# Frequenzweiche.net
KiCad netlist of a schematic drawn in Altium Designer
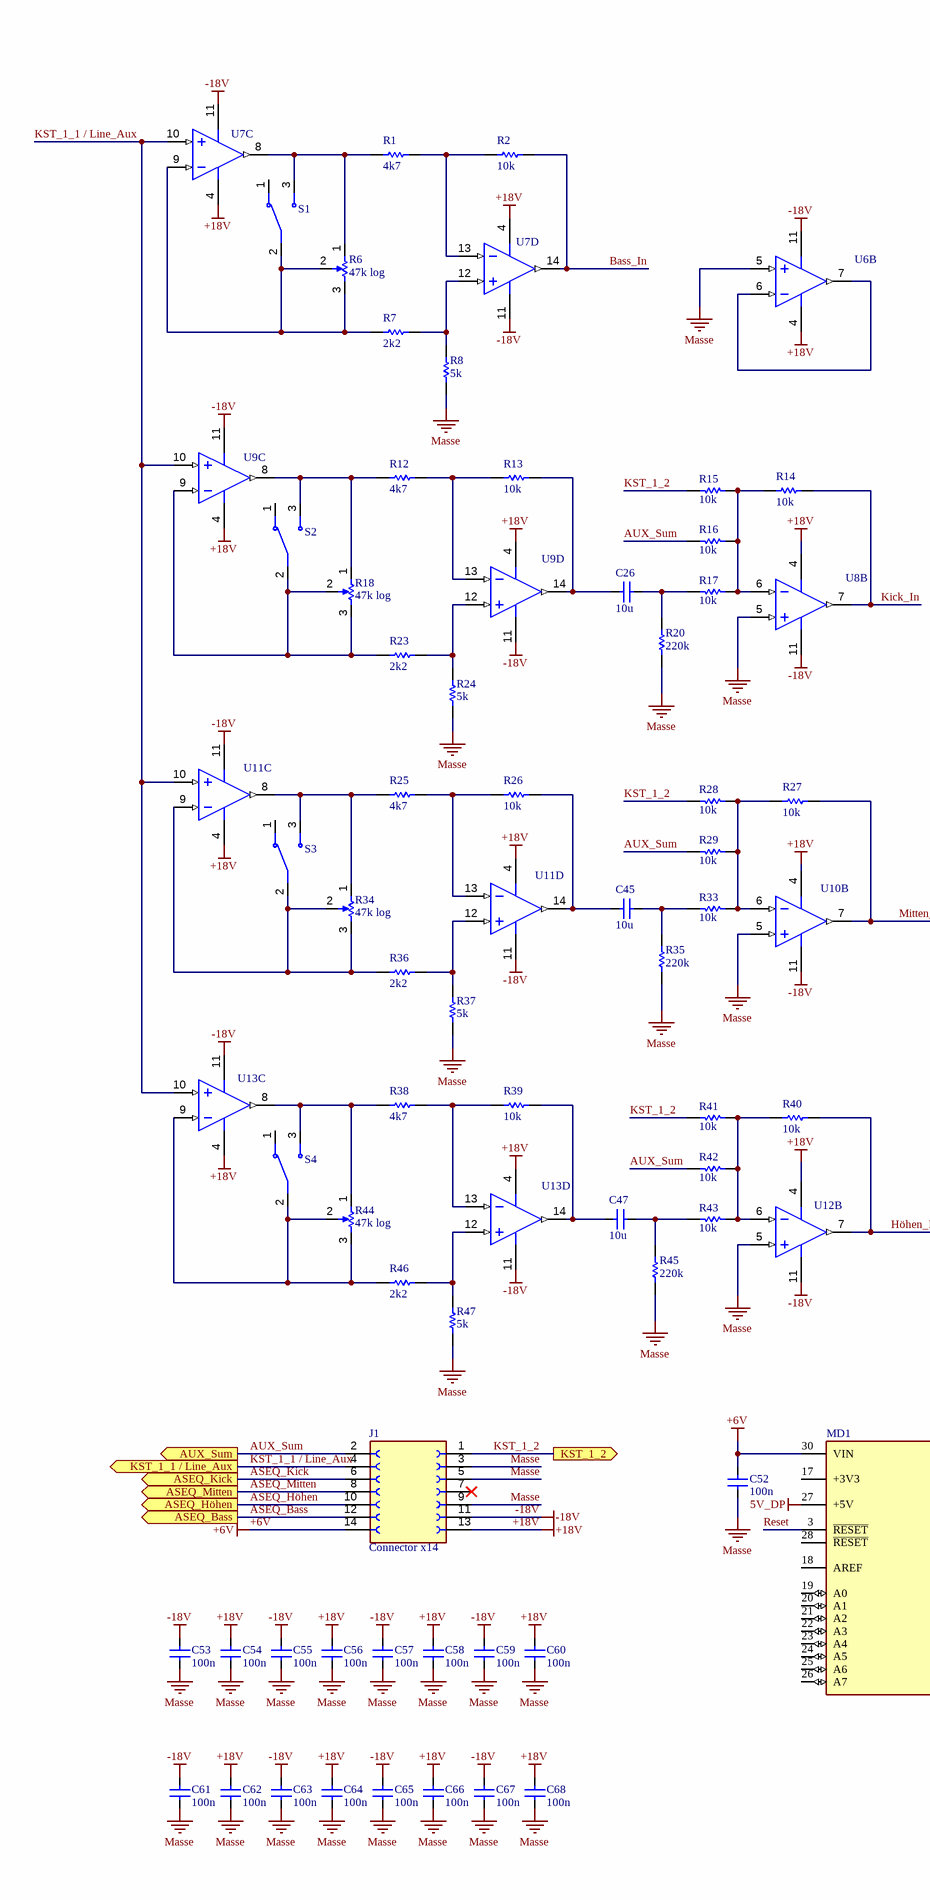
[diagram p0: Frequenzweiche.SchDoc, left]
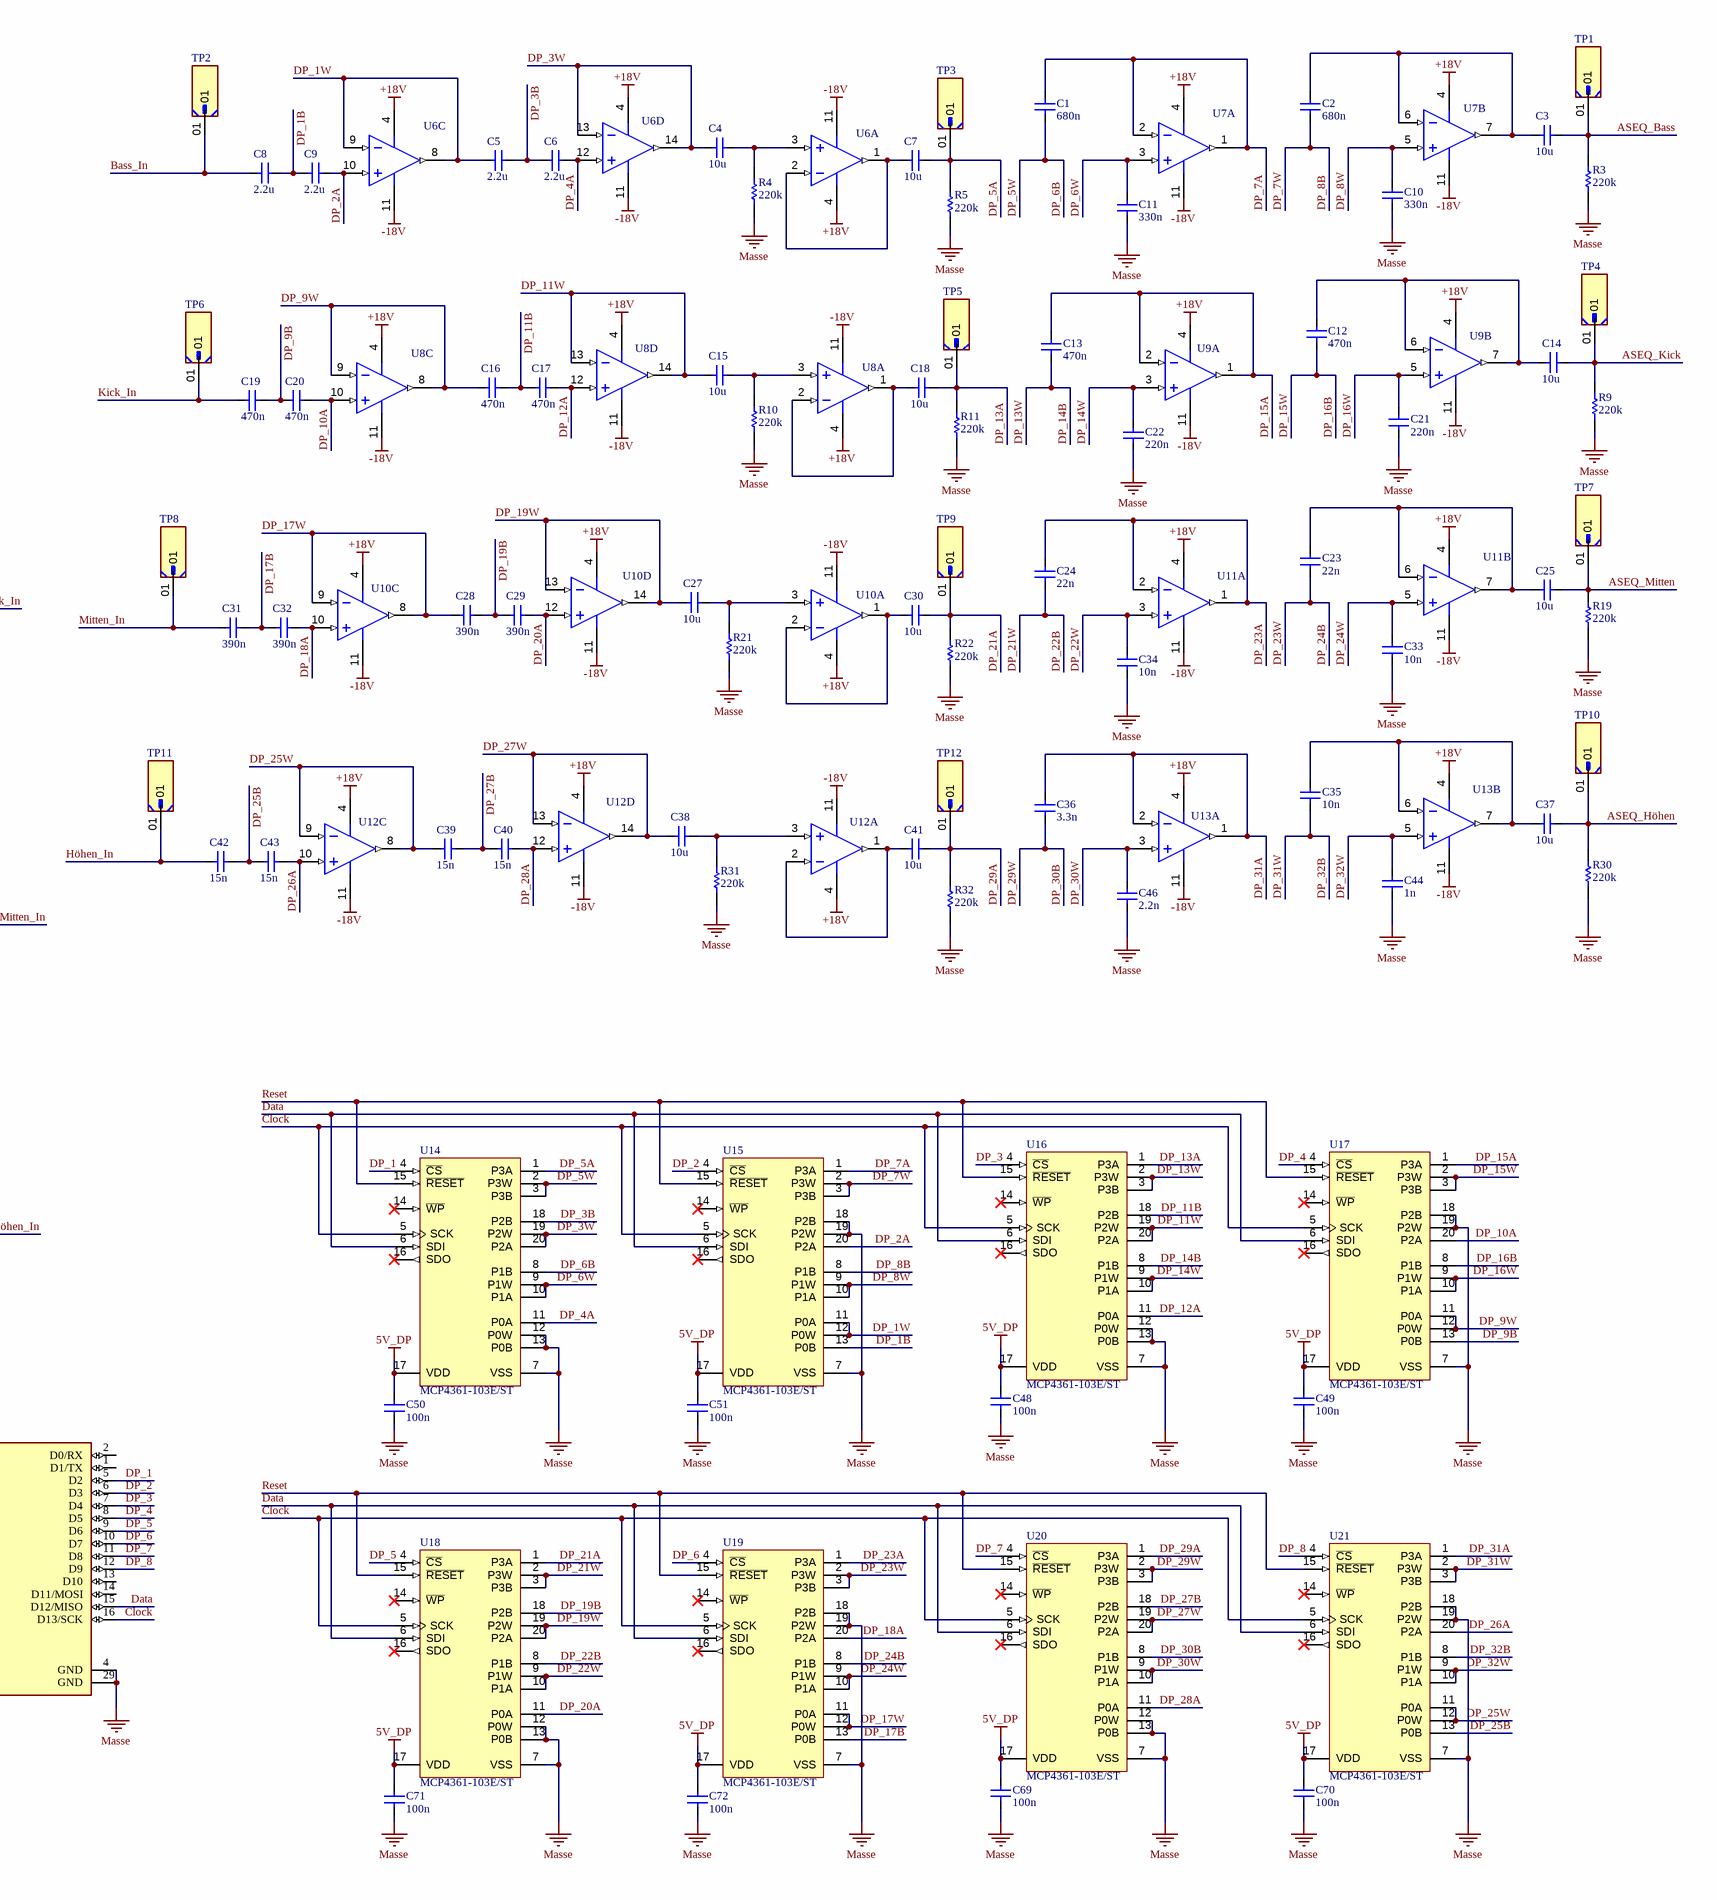
[diagram p1: Frequenzweiche.SchDoc, right]

(export (version "E")
  (design (tool "Eeschema 10.0.6"))
  (components
    (comp (ref "C1")
      (value "680n")
      (footprint "0805")
      (description "0805 Kondensator")
      (libsource (lib "Bauteile") (part "0805 Kondensator"))
    )
    (comp (ref "C2")
      (value "680n")
      (footprint "0805")
      (description "0805 Kondensator")
      (libsource (lib "Bauteile") (part "0805 Kondensator"))
    )
    (comp (ref "C3")
      (value "10u")
      (footprint "0805")
      (description "0805 Kondensator")
      (libsource (lib "Bauteile") (part "0805 Kondensator"))
    )
    (comp (ref "C4")
      (value "10u")
      (footprint "0805")
      (description "0805 Kondensator")
      (libsource (lib "Bauteile") (part "0805 Kondensator"))
    )
    (comp (ref "C5")
      (value "2.2u")
      (footprint "0805")
      (description "0805 Kondensator")
      (libsource (lib "Bauteile") (part "0805 Kondensator"))
    )
    (comp (ref "C6")
      (value "2.2u")
      (footprint "0805")
      (description "0805 Kondensator")
      (libsource (lib "Bauteile") (part "0805 Kondensator"))
    )
    (comp (ref "C7")
      (value "10u")
      (footprint "0805")
      (description "0805 Kondensator")
      (libsource (lib "Bauteile") (part "0805 Kondensator"))
    )
    (comp (ref "C8")
      (value "2.2u")
      (footprint "0805")
      (description "0805 Kondensator")
      (libsource (lib "Bauteile") (part "0805 Kondensator"))
    )
    (comp (ref "C9")
      (value "2.2u")
      (footprint "0805")
      (description "0805 Kondensator")
      (libsource (lib "Bauteile") (part "0805 Kondensator"))
    )
    (comp (ref "C10")
      (value "330n")
      (footprint "0805")
      (description "0805 Kondensator")
      (libsource (lib "Bauteile") (part "0805 Kondensator"))
    )
    (comp (ref "C11")
      (value "330n")
      (footprint "0805")
      (description "0805 Kondensator")
      (libsource (lib "Bauteile") (part "0805 Kondensator"))
    )
    (comp (ref "C12")
      (value "470n")
      (footprint "0805")
      (description "0805 Kondensator")
      (libsource (lib "Bauteile") (part "0805 Kondensator"))
    )
    (comp (ref "C13")
      (value "470n")
      (footprint "0805")
      (description "0805 Kondensator")
      (libsource (lib "Bauteile") (part "0805 Kondensator"))
    )
    (comp (ref "C14")
      (value "10u")
      (footprint "0805")
      (description "0805 Kondensator")
      (libsource (lib "Bauteile") (part "0805 Kondensator"))
    )
    (comp (ref "C15")
      (value "10u")
      (footprint "0805")
      (description "0805 Kondensator")
      (libsource (lib "Bauteile") (part "0805 Kondensator"))
    )
    (comp (ref "C16")
      (value "470n")
      (footprint "0805")
      (description "0805 Kondensator")
      (libsource (lib "Bauteile") (part "0805 Kondensator"))
    )
    (comp (ref "C17")
      (value "470n")
      (footprint "0805")
      (description "0805 Kondensator")
      (libsource (lib "Bauteile") (part "0805 Kondensator"))
    )
    (comp (ref "C18")
      (value "10u")
      (footprint "0805")
      (description "0805 Kondensator")
      (libsource (lib "Bauteile") (part "0805 Kondensator"))
    )
    (comp (ref "C19")
      (value "470n")
      (footprint "0805")
      (description "0805 Kondensator")
      (libsource (lib "Bauteile") (part "0805 Kondensator"))
    )
    (comp (ref "C20")
      (value "470n")
      (footprint "0805")
      (description "0805 Kondensator")
      (libsource (lib "Bauteile") (part "0805 Kondensator"))
    )
    (comp (ref "C21")
      (value "220n")
      (footprint "0805")
      (description "0805 Kondensator")
      (libsource (lib "Bauteile") (part "0805 Kondensator"))
    )
    (comp (ref "C22")
      (value "220n")
      (footprint "0805")
      (description "0805 Kondensator")
      (libsource (lib "Bauteile") (part "0805 Kondensator"))
    )
    (comp (ref "C23")
      (value "22n")
      (footprint "0805")
      (description "0805 Kondensator")
      (libsource (lib "Bauteile") (part "0805 Kondensator"))
    )
    (comp (ref "C24")
      (value "22n")
      (footprint "0805")
      (description "0805 Kondensator")
      (libsource (lib "Bauteile") (part "0805 Kondensator"))
    )
    (comp (ref "C25")
      (value "10u")
      (footprint "0805")
      (description "0805 Kondensator")
      (libsource (lib "Bauteile") (part "0805 Kondensator"))
    )
    (comp (ref "C26")
      (value "10u")
      (footprint "0805")
      (description "0805 Kondensator")
      (libsource (lib "Bauteile") (part "0805 Kondensator"))
    )
    (comp (ref "C27")
      (value "10u")
      (footprint "0805")
      (description "0805 Kondensator")
      (libsource (lib "Bauteile") (part "0805 Kondensator"))
    )
    (comp (ref "C28")
      (value "390n")
      (footprint "0805")
      (description "0805 Kondensator")
      (libsource (lib "Bauteile") (part "0805 Kondensator"))
    )
    (comp (ref "C29")
      (value "390n")
      (footprint "0805")
      (description "0805 Kondensator")
      (libsource (lib "Bauteile") (part "0805 Kondensator"))
    )
    (comp (ref "C30")
      (value "10u")
      (footprint "0805")
      (description "0805 Kondensator")
      (libsource (lib "Bauteile") (part "0805 Kondensator"))
    )
    (comp (ref "C31")
      (value "390n")
      (footprint "0805")
      (description "0805 Kondensator")
      (libsource (lib "Bauteile") (part "0805 Kondensator"))
    )
    (comp (ref "C32")
      (value "390n")
      (footprint "0805")
      (description "0805 Kondensator")
      (libsource (lib "Bauteile") (part "0805 Kondensator"))
    )
    (comp (ref "C33")
      (value "10n")
      (footprint "0805")
      (description "0805 Kondensator")
      (libsource (lib "Bauteile") (part "0805 Kondensator"))
    )
    (comp (ref "C34")
      (value "10n")
      (footprint "0805")
      (description "0805 Kondensator")
      (libsource (lib "Bauteile") (part "0805 Kondensator"))
    )
    (comp (ref "C35")
      (value "10n")
      (footprint "0805")
      (description "0805 Kondensator")
      (libsource (lib "Bauteile") (part "0805 Kondensator"))
    )
    (comp (ref "C36")
      (value "3.3n")
      (footprint "0805")
      (description "0805 Kondensator")
      (libsource (lib "Bauteile") (part "0805 Kondensator"))
    )
    (comp (ref "C37")
      (value "10u")
      (footprint "0805")
      (description "0805 Kondensator")
      (libsource (lib "Bauteile") (part "0805 Kondensator"))
    )
    (comp (ref "C38")
      (value "10u")
      (footprint "0805")
      (description "0805 Kondensator")
      (libsource (lib "Bauteile") (part "0805 Kondensator"))
    )
    (comp (ref "C39")
      (value "15n")
      (footprint "0805")
      (description "0805 Kondensator")
      (libsource (lib "Bauteile") (part "0805 Kondensator"))
    )
    (comp (ref "C40")
      (value "15n")
      (footprint "0805")
      (description "0805 Kondensator")
      (libsource (lib "Bauteile") (part "0805 Kondensator"))
    )
    (comp (ref "C41")
      (value "10u")
      (footprint "0805")
      (description "0805 Kondensator")
      (libsource (lib "Bauteile") (part "0805 Kondensator"))
    )
    (comp (ref "C42")
      (value "15n")
      (footprint "0805")
      (description "0805 Kondensator")
      (libsource (lib "Bauteile") (part "0805 Kondensator"))
    )
    (comp (ref "C43")
      (value "15n")
      (footprint "0805")
      (description "0805 Kondensator")
      (libsource (lib "Bauteile") (part "0805 Kondensator"))
    )
    (comp (ref "C44")
      (value "1n")
      (footprint "0805")
      (description "0805 Kondensator")
      (libsource (lib "Bauteile") (part "0805 Kondensator"))
    )
    (comp (ref "C45")
      (value "10u")
      (footprint "0805")
      (description "0805 Kondensator")
      (libsource (lib "Bauteile") (part "0805 Kondensator"))
    )
    (comp (ref "C46")
      (value "2.2n")
      (footprint "0805")
      (description "0805 Kondensator")
      (libsource (lib "Bauteile") (part "0805 Kondensator"))
    )
    (comp (ref "C47")
      (value "10u")
      (footprint "0805")
      (description "0805 Kondensator")
      (libsource (lib "Bauteile") (part "0805 Kondensator"))
    )
    (comp (ref "C48")
      (value "100n")
      (footprint "0805")
      (description "0805 Kondensator")
      (libsource (lib "Bauteile") (part "0805 Kondensator"))
    )
    (comp (ref "C49")
      (value "100n")
      (footprint "0805")
      (description "0805 Kondensator")
      (libsource (lib "Bauteile") (part "0805 Kondensator"))
    )
    (comp (ref "C50")
      (value "100n")
      (footprint "0805")
      (description "0805 Kondensator")
      (libsource (lib "Bauteile") (part "0805 Kondensator"))
    )
    (comp (ref "C51")
      (value "100n")
      (footprint "0805")
      (description "0805 Kondensator")
      (libsource (lib "Bauteile") (part "0805 Kondensator"))
    )
    (comp (ref "C52")
      (value "100n")
      (footprint "0805")
      (description "0805 Kondensator")
      (libsource (lib "Bauteile") (part "0805 Kondensator"))
    )
    (comp (ref "C53")
      (value "100n")
      (footprint "0805")
      (description "0805 Kondensator")
      (libsource (lib "Bauteile") (part "0805 Kondensator"))
    )
    (comp (ref "C54")
      (value "100n")
      (footprint "0805")
      (description "0805 Kondensator")
      (libsource (lib "Bauteile") (part "0805 Kondensator"))
    )
    (comp (ref "C55")
      (value "100n")
      (footprint "0805")
      (description "0805 Kondensator")
      (libsource (lib "Bauteile") (part "0805 Kondensator"))
    )
    (comp (ref "C56")
      (value "100n")
      (footprint "0805")
      (description "0805 Kondensator")
      (libsource (lib "Bauteile") (part "0805 Kondensator"))
    )
    (comp (ref "C57")
      (value "100n")
      (footprint "0805")
      (description "0805 Kondensator")
      (libsource (lib "Bauteile") (part "0805 Kondensator"))
    )
    (comp (ref "C58")
      (value "100n")
      (footprint "0805")
      (description "0805 Kondensator")
      (libsource (lib "Bauteile") (part "0805 Kondensator"))
    )
    (comp (ref "C59")
      (value "100n")
      (footprint "0805")
      (description "0805 Kondensator")
      (libsource (lib "Bauteile") (part "0805 Kondensator"))
    )
    (comp (ref "C60")
      (value "100n")
      (footprint "0805")
      (description "0805 Kondensator")
      (libsource (lib "Bauteile") (part "0805 Kondensator"))
    )
    (comp (ref "C61")
      (value "100n")
      (footprint "0805")
      (description "0805 Kondensator")
      (libsource (lib "Bauteile") (part "0805 Kondensator"))
    )
    (comp (ref "C62")
      (value "100n")
      (footprint "0805")
      (description "0805 Kondensator")
      (libsource (lib "Bauteile") (part "0805 Kondensator"))
    )
    (comp (ref "C63")
      (value "100n")
      (footprint "0805")
      (description "0805 Kondensator")
      (libsource (lib "Bauteile") (part "0805 Kondensator"))
    )
    (comp (ref "C64")
      (value "100n")
      (footprint "0805")
      (description "0805 Kondensator")
      (libsource (lib "Bauteile") (part "0805 Kondensator"))
    )
    (comp (ref "C65")
      (value "100n")
      (footprint "0805")
      (description "0805 Kondensator")
      (libsource (lib "Bauteile") (part "0805 Kondensator"))
    )
    (comp (ref "C66")
      (value "100n")
      (footprint "0805")
      (description "0805 Kondensator")
      (libsource (lib "Bauteile") (part "0805 Kondensator"))
    )
    (comp (ref "C67")
      (value "100n")
      (footprint "0805")
      (description "0805 Kondensator")
      (libsource (lib "Bauteile") (part "0805 Kondensator"))
    )
    (comp (ref "C68")
      (value "100n")
      (footprint "0805")
      (description "0805 Kondensator")
      (libsource (lib "Bauteile") (part "0805 Kondensator"))
    )
    (comp (ref "C69")
      (value "100n")
      (footprint "0805")
      (description "0805 Kondensator")
      (libsource (lib "Bauteile") (part "0805 Kondensator"))
    )
    (comp (ref "C70")
      (value "100n")
      (footprint "0805")
      (description "0805 Kondensator")
      (libsource (lib "Bauteile") (part "0805 Kondensator"))
    )
    (comp (ref "C71")
      (value "100n")
      (footprint "0805")
      (description "0805 Kondensator")
      (libsource (lib "Bauteile") (part "0805 Kondensator"))
    )
    (comp (ref "C72")
      (value "100n")
      (footprint "0805")
      (description "0805 Kondensator")
      (libsource (lib "Bauteile") (part "0805 Kondensator"))
    )
    (comp (ref "J1")
      (value "Connector x14")
      (footprint "Connector x14")
      (description "14 Position Header Connector Through Hole")
      (fields (field (name "MF") "Sullins Connector") (field (name "MP") "SFH11-PBPC-D07-ST-BK"))
      (libsource (lib "Bauteile") (part "Connector x14"))
    )
    (comp (ref "MD1")
      (value "A000005")
      (footprint "Arduino Nano")
      (description "ARDUINO NANO ATMEGA328 EVAL BRD")
      (libsource (lib "Bauteile") (part "Arduino Nano"))
    )
    (comp (ref "R1")
      (value "4k7")
      (footprint "0805")
      (description "0805 Widerstand")
      (libsource (lib "Bauteile") (part "0805 Widerstand"))
    )
    (comp (ref "R2")
      (value "10k")
      (footprint "0805")
      (description "0805 Widerstand")
      (libsource (lib "Bauteile") (part "0805 Widerstand"))
    )
    (comp (ref "R3")
      (value "220k")
      (footprint "0805")
      (description "0805 Widerstand")
      (libsource (lib "Bauteile") (part "0805 Widerstand"))
    )
    (comp (ref "R4")
      (value "220k")
      (footprint "0805")
      (description "0805 Widerstand")
      (libsource (lib "Bauteile") (part "0805 Widerstand"))
    )
    (comp (ref "R5")
      (value "220k")
      (footprint "0805")
      (description "0805 Widerstand")
      (libsource (lib "Bauteile") (part "0805 Widerstand"))
    )
    (comp (ref "R6")
      (value "47k log")
      (footprint "Connector x3")
      (description "Potentiometer")
      (libsource (lib "Bauteile") (part "Potentiometer Buchsenleiste"))
    )
    (comp (ref "R7")
      (value "2k2")
      (footprint "0805")
      (description "0805 Widerstand")
      (libsource (lib "Bauteile") (part "0805 Widerstand"))
    )
    (comp (ref "R8")
      (value "5k")
      (footprint "0805")
      (description "0805 Widerstand")
      (libsource (lib "Bauteile") (part "0805 Widerstand"))
    )
    (comp (ref "R9")
      (value "220k")
      (footprint "0805")
      (description "0805 Widerstand")
      (libsource (lib "Bauteile") (part "0805 Widerstand"))
    )
    (comp (ref "R10")
      (value "220k")
      (footprint "0805")
      (description "0805 Widerstand")
      (libsource (lib "Bauteile") (part "0805 Widerstand"))
    )
    (comp (ref "R11")
      (value "220k")
      (footprint "0805")
      (description "0805 Widerstand")
      (libsource (lib "Bauteile") (part "0805 Widerstand"))
    )
    (comp (ref "R12")
      (value "4k7")
      (footprint "0805")
      (description "0805 Widerstand")
      (libsource (lib "Bauteile") (part "0805 Widerstand"))
    )
    (comp (ref "R13")
      (value "10k")
      (footprint "0805")
      (description "0805 Widerstand")
      (libsource (lib "Bauteile") (part "0805 Widerstand"))
    )
    (comp (ref "R14")
      (value "10k")
      (footprint "0805")
      (description "0805 Widerstand")
      (libsource (lib "Bauteile") (part "0805 Widerstand"))
    )
    (comp (ref "R15")
      (value "10k")
      (footprint "0805")
      (description "0805 Widerstand")
      (libsource (lib "Bauteile") (part "0805 Widerstand"))
    )
    (comp (ref "R16")
      (value "10k")
      (footprint "0805")
      (description "0805 Widerstand")
      (libsource (lib "Bauteile") (part "0805 Widerstand"))
    )
    (comp (ref "R17")
      (value "10k")
      (footprint "0805")
      (description "0805 Widerstand")
      (libsource (lib "Bauteile") (part "0805 Widerstand"))
    )
    (comp (ref "R18")
      (value "47k log")
      (footprint "Connector x3")
      (description "Potentiometer")
      (libsource (lib "Bauteile") (part "Potentiometer Buchsenleiste"))
    )
    (comp (ref "R19")
      (value "220k")
      (footprint "0805")
      (description "0805 Widerstand")
      (libsource (lib "Bauteile") (part "0805 Widerstand"))
    )
    (comp (ref "R20")
      (value "220k")
      (footprint "0805")
      (description "0805 Widerstand")
      (libsource (lib "Bauteile") (part "0805 Widerstand"))
    )
    (comp (ref "R21")
      (value "220k")
      (footprint "0805")
      (description "0805 Widerstand")
      (libsource (lib "Bauteile") (part "0805 Widerstand"))
    )
    (comp (ref "R22")
      (value "220k")
      (footprint "0805")
      (description "0805 Widerstand")
      (libsource (lib "Bauteile") (part "0805 Widerstand"))
    )
    (comp (ref "R23")
      (value "2k2")
      (footprint "0805")
      (description "0805 Widerstand")
      (libsource (lib "Bauteile") (part "0805 Widerstand"))
    )
    (comp (ref "R24")
      (value "5k")
      (footprint "0805")
      (description "0805 Widerstand")
      (libsource (lib "Bauteile") (part "0805 Widerstand"))
    )
    (comp (ref "R25")
      (value "4k7")
      (footprint "0805")
      (description "0805 Widerstand")
      (libsource (lib "Bauteile") (part "0805 Widerstand"))
    )
    (comp (ref "R26")
      (value "10k")
      (footprint "0805")
      (description "0805 Widerstand")
      (libsource (lib "Bauteile") (part "0805 Widerstand"))
    )
    (comp (ref "R27")
      (value "10k")
      (footprint "0805")
      (description "0805 Widerstand")
      (libsource (lib "Bauteile") (part "0805 Widerstand"))
    )
    (comp (ref "R28")
      (value "10k")
      (footprint "0805")
      (description "0805 Widerstand")
      (libsource (lib "Bauteile") (part "0805 Widerstand"))
    )
    (comp (ref "R29")
      (value "10k")
      (footprint "0805")
      (description "0805 Widerstand")
      (libsource (lib "Bauteile") (part "0805 Widerstand"))
    )
    (comp (ref "R30")
      (value "220k")
      (footprint "0805")
      (description "0805 Widerstand")
      (libsource (lib "Bauteile") (part "0805 Widerstand"))
    )
    (comp (ref "R31")
      (value "220k")
      (footprint "0805")
      (description "0805 Widerstand")
      (libsource (lib "Bauteile") (part "0805 Widerstand"))
    )
    (comp (ref "R32")
      (value "220k")
      (footprint "0805")
      (description "0805 Widerstand")
      (libsource (lib "Bauteile") (part "0805 Widerstand"))
    )
    (comp (ref "R33")
      (value "10k")
      (footprint "0805")
      (description "0805 Widerstand")
      (libsource (lib "Bauteile") (part "0805 Widerstand"))
    )
    (comp (ref "R34")
      (value "47k log")
      (footprint "Connector x3")
      (description "Potentiometer")
      (libsource (lib "Bauteile") (part "Potentiometer Buchsenleiste"))
    )
    (comp (ref "R35")
      (value "220k")
      (footprint "0805")
      (description "0805 Widerstand")
      (libsource (lib "Bauteile") (part "0805 Widerstand"))
    )
    (comp (ref "R36")
      (value "2k2")
      (footprint "0805")
      (description "0805 Widerstand")
      (libsource (lib "Bauteile") (part "0805 Widerstand"))
    )
    (comp (ref "R37")
      (value "5k")
      (footprint "0805")
      (description "0805 Widerstand")
      (libsource (lib "Bauteile") (part "0805 Widerstand"))
    )
    (comp (ref "R38")
      (value "4k7")
      (footprint "0805")
      (description "0805 Widerstand")
      (libsource (lib "Bauteile") (part "0805 Widerstand"))
    )
    (comp (ref "R39")
      (value "10k")
      (footprint "0805")
      (description "0805 Widerstand")
      (libsource (lib "Bauteile") (part "0805 Widerstand"))
    )
    (comp (ref "R40")
      (value "10k")
      (footprint "0805")
      (description "0805 Widerstand")
      (libsource (lib "Bauteile") (part "0805 Widerstand"))
    )
    (comp (ref "R41")
      (value "10k")
      (footprint "0805")
      (description "0805 Widerstand")
      (libsource (lib "Bauteile") (part "0805 Widerstand"))
    )
    (comp (ref "R42")
      (value "10k")
      (footprint "0805")
      (description "0805 Widerstand")
      (libsource (lib "Bauteile") (part "0805 Widerstand"))
    )
    (comp (ref "R43")
      (value "10k")
      (footprint "0805")
      (description "0805 Widerstand")
      (libsource (lib "Bauteile") (part "0805 Widerstand"))
    )
    (comp (ref "R44")
      (value "47k log")
      (footprint "Connector x3")
      (description "Potentiometer")
      (libsource (lib "Bauteile") (part "Potentiometer Buchsenleiste"))
    )
    (comp (ref "R45")
      (value "220k")
      (footprint "0805")
      (description "0805 Widerstand")
      (libsource (lib "Bauteile") (part "0805 Widerstand"))
    )
    (comp (ref "R46")
      (value "2k2")
      (footprint "0805")
      (description "0805 Widerstand")
      (libsource (lib "Bauteile") (part "0805 Widerstand"))
    )
    (comp (ref "R47")
      (value "5k")
      (footprint "0805")
      (description "0805 Widerstand")
      (libsource (lib "Bauteile") (part "0805 Widerstand"))
    )
    (comp (ref "S1")
      (value "Schalter Buchsenleiste")
      (footprint "Connector x3")
      (description "Toggle Switch SPDT Through Hole")
      (fields (field (name "MP") "100SP1T1B4M2QE"))
      (libsource (lib "Bauteile") (part "Schalter Buchsenleiste"))
    )
    (comp (ref "S2")
      (value "Schalter Buchsenleiste")
      (footprint "Connector x3")
      (description "Toggle Switch SPDT Through Hole")
      (fields (field (name "MP") "100SP1T1B4M2QE"))
      (libsource (lib "Bauteile") (part "Schalter Buchsenleiste"))
    )
    (comp (ref "S3")
      (value "Schalter Buchsenleiste")
      (footprint "Connector x3")
      (description "Toggle Switch SPDT Through Hole")
      (fields (field (name "MP") "100SP1T1B4M2QE"))
      (libsource (lib "Bauteile") (part "Schalter Buchsenleiste"))
    )
    (comp (ref "S4")
      (value "Schalter Buchsenleiste")
      (footprint "Connector x3")
      (description "Toggle Switch SPDT Through Hole")
      (fields (field (name "MP") "100SP1T1B4M2QE"))
      (libsource (lib "Bauteile") (part "Schalter Buchsenleiste"))
    )
    (comp (ref "TP1")
      (value "Test_Pin")
      (footprint "Test_Pin")
      (description "Connector Header Through Hole 2 position 0.100 (2.54mm)")
      (fields (field (name "MF") "Wurth Elektronik") (field (name "MP") "61300211121"))
      (libsource (lib "Bauteile") (part "Test_Pin"))
    )
    (comp (ref "TP2")
      (value "Test_Pin")
      (footprint "Test_Pin")
      (description "Connector Header Through Hole 2 position 0.100 (2.54mm)")
      (fields (field (name "MF") "Wurth Elektronik") (field (name "MP") "61300211121"))
      (libsource (lib "Bauteile") (part "Test_Pin"))
    )
    (comp (ref "TP3")
      (value "Test_Pin")
      (footprint "Test_Pin")
      (description "Connector Header Through Hole 2 position 0.100 (2.54mm)")
      (fields (field (name "MF") "Wurth Elektronik") (field (name "MP") "61300211121"))
      (libsource (lib "Bauteile") (part "Test_Pin"))
    )
    (comp (ref "TP4")
      (value "Test_Pin")
      (footprint "Test_Pin")
      (description "Connector Header Through Hole 2 position 0.100 (2.54mm)")
      (fields (field (name "MF") "Wurth Elektronik") (field (name "MP") "61300211121"))
      (libsource (lib "Bauteile") (part "Test_Pin"))
    )
    (comp (ref "TP5")
      (value "Test_Pin")
      (footprint "Test_Pin")
      (description "Connector Header Through Hole 2 position 0.100 (2.54mm)")
      (fields (field (name "MF") "Wurth Elektronik") (field (name "MP") "61300211121"))
      (libsource (lib "Bauteile") (part "Test_Pin"))
    )
    (comp (ref "TP6")
      (value "Test_Pin")
      (footprint "Test_Pin")
      (description "Connector Header Through Hole 2 position 0.100 (2.54mm)")
      (fields (field (name "MF") "Wurth Elektronik") (field (name "MP") "61300211121"))
      (libsource (lib "Bauteile") (part "Test_Pin"))
    )
    (comp (ref "TP7")
      (value "Test_Pin")
      (footprint "Test_Pin")
      (description "Connector Header Through Hole 2 position 0.100 (2.54mm)")
      (fields (field (name "MF") "Wurth Elektronik") (field (name "MP") "61300211121"))
      (libsource (lib "Bauteile") (part "Test_Pin"))
    )
    (comp (ref "TP8")
      (value "Test_Pin")
      (footprint "Test_Pin")
      (description "Connector Header Through Hole 2 position 0.100 (2.54mm)")
      (fields (field (name "MF") "Wurth Elektronik") (field (name "MP") "61300211121"))
      (libsource (lib "Bauteile") (part "Test_Pin"))
    )
    (comp (ref "TP9")
      (value "Test_Pin")
      (footprint "Test_Pin")
      (description "Connector Header Through Hole 2 position 0.100 (2.54mm)")
      (fields (field (name "MF") "Wurth Elektronik") (field (name "MP") "61300211121"))
      (libsource (lib "Bauteile") (part "Test_Pin"))
    )
    (comp (ref "TP10")
      (value "Test_Pin")
      (footprint "Test_Pin")
      (description "Connector Header Through Hole 2 position 0.100 (2.54mm)")
      (fields (field (name "MF") "Wurth Elektronik") (field (name "MP") "61300211121"))
      (libsource (lib "Bauteile") (part "Test_Pin"))
    )
    (comp (ref "TP11")
      (value "Test_Pin")
      (footprint "Test_Pin")
      (description "Connector Header Through Hole 2 position 0.100 (2.54mm)")
      (fields (field (name "MF") "Wurth Elektronik") (field (name "MP") "61300211121"))
      (libsource (lib "Bauteile") (part "Test_Pin"))
    )
    (comp (ref "TP12")
      (value "Test_Pin")
      (footprint "Test_Pin")
      (description "Connector Header Through Hole 2 position 0.100 (2.54mm)")
      (fields (field (name "MF") "Wurth Elektronik") (field (name "MP") "61300211121"))
      (libsource (lib "Bauteile") (part "Test_Pin"))
    )
    (comp (ref "U6")
      (value "OPA4134UA")
      (footprint "DIP14 IC Socket")
      (fields (field (name "MANUFACTURER") "Texas Instruments"))
      (libsource (lib "Bauteile") (part "SOIC OPA4134UA"))
    )
    (comp (ref "U7")
      (value "OPA4134UA")
      (footprint "DIP14 IC Socket")
      (fields (field (name "MANUFACTURER") "Texas Instruments"))
      (libsource (lib "Bauteile") (part "SOIC OPA4134UA"))
    )
    (comp (ref "U8")
      (value "OPA4134UA")
      (footprint "DIP14 IC Socket")
      (fields (field (name "MANUFACTURER") "Texas Instruments"))
      (libsource (lib "Bauteile") (part "SOIC OPA4134UA"))
    )
    (comp (ref "U9")
      (value "OPA4134UA")
      (footprint "DIP14 IC Socket")
      (fields (field (name "MANUFACTURER") "Texas Instruments"))
      (libsource (lib "Bauteile") (part "SOIC OPA4134UA"))
    )
    (comp (ref "U10")
      (value "OPA4134UA")
      (footprint "DIP14 IC Socket")
      (fields (field (name "MANUFACTURER") "Texas Instruments"))
      (libsource (lib "Bauteile") (part "SOIC OPA4134UA"))
    )
    (comp (ref "U11")
      (value "OPA4134UA")
      (footprint "DIP14 IC Socket")
      (fields (field (name "MANUFACTURER") "Texas Instruments"))
      (libsource (lib "Bauteile") (part "SOIC OPA4134UA"))
    )
    (comp (ref "U12")
      (value "OPA4134UA")
      (footprint "DIP14 IC Socket")
      (fields (field (name "MANUFACTURER") "Texas Instruments"))
      (libsource (lib "Bauteile") (part "SOIC OPA4134UA"))
    )
    (comp (ref "U13")
      (value "OPA4134UA")
      (footprint "DIP14 IC Socket")
      (fields (field (name "MANUFACTURER") "Texas Instruments"))
      (libsource (lib "Bauteile") (part "SOIC OPA4134UA"))
    )
    (comp (ref "U14")
      (value "MCP4361-103E/ST")
      (footprint "MCP 4361")
      (description "7/8-Bit Quad SPI Digital POT with Non-Volatile Memory, 20-Pin TSSOP, Extended Temperature")
      (libsource (lib "Bauteile") (part "MCP 4361"))
    )
    (comp (ref "U15")
      (value "MCP4361-103E/ST")
      (footprint "MCP 4361")
      (description "7/8-Bit Quad SPI Digital POT with Non-Volatile Memory, 20-Pin TSSOP, Extended Temperature")
      (libsource (lib "Bauteile") (part "MCP 4361"))
    )
    (comp (ref "U16")
      (value "MCP4361-103E/ST")
      (footprint "MCP 4361")
      (description "7/8-Bit Quad SPI Digital POT with Non-Volatile Memory, 20-Pin TSSOP, Extended Temperature")
      (libsource (lib "Bauteile") (part "MCP 4361"))
    )
    (comp (ref "U17")
      (value "MCP4361-103E/ST")
      (footprint "MCP 4361")
      (description "7/8-Bit Quad SPI Digital POT with Non-Volatile Memory, 20-Pin TSSOP, Extended Temperature")
      (libsource (lib "Bauteile") (part "MCP 4361"))
    )
    (comp (ref "U18")
      (value "MCP4361-103E/ST")
      (footprint "MCP 4361")
      (description "7/8-Bit Quad SPI Digital POT with Non-Volatile Memory, 20-Pin TSSOP, Extended Temperature")
      (libsource (lib "Bauteile") (part "MCP 4361"))
    )
    (comp (ref "U19")
      (value "MCP4361-103E/ST")
      (footprint "MCP 4361")
      (description "7/8-Bit Quad SPI Digital POT with Non-Volatile Memory, 20-Pin TSSOP, Extended Temperature")
      (libsource (lib "Bauteile") (part "MCP 4361"))
    )
    (comp (ref "U20")
      (value "MCP4361-103E/ST")
      (footprint "MCP 4361")
      (description "7/8-Bit Quad SPI Digital POT with Non-Volatile Memory, 20-Pin TSSOP, Extended Temperature")
      (libsource (lib "Bauteile") (part "MCP 4361"))
    )
    (comp (ref "U21")
      (value "MCP4361-103E/ST")
      (footprint "MCP 4361")
      (description "7/8-Bit Quad SPI Digital POT with Non-Volatile Memory, 20-Pin TSSOP, Extended Temperature")
      (libsource (lib "Bauteile") (part "MCP 4361"))
    )
  )
  (nets
    (net (code "1") (name "+6V") (class "Default")
      (node (ref "C52") (pin "2") (pinfunction "2_2") (pintype "passive"))
      (node (ref "J1") (pin "14") (pinfunction "14_14") (pintype "passive"))
      (node (ref "MD1") (pin "30") (pinfunction "VIN_30") (pintype "power_in"))
    )
    (net (code "2") (name "+18V") (class "Default")
      (node (ref "C54") (pin "2") (pinfunction "2_2") (pintype "passive"))
      (node (ref "C56") (pin "2") (pinfunction "2_2") (pintype "passive"))
      (node (ref "C58") (pin "2") (pinfunction "2_2") (pintype "passive"))
      (node (ref "C60") (pin "2") (pinfunction "2_2") (pintype "passive"))
      (node (ref "C62") (pin "2") (pinfunction "2_2") (pintype "passive"))
      (node (ref "C64") (pin "2") (pinfunction "2_2") (pintype "passive"))
      (node (ref "C66") (pin "2") (pinfunction "2_2") (pintype "passive"))
      (node (ref "C68") (pin "2") (pinfunction "2_2") (pintype "passive"))
      (node (ref "J1") (pin "13") (pinfunction "13_13") (pintype "passive"))
      (node (ref "U10") (pin "4") (pinfunction "V+_4") (pintype "power_in"))
      (node (ref "U11") (pin "4") (pinfunction "V+_4") (pintype "power_in"))
      (node (ref "U12") (pin "4") (pinfunction "V+_4") (pintype "power_in"))
      (node (ref "U13") (pin "4") (pinfunction "V+_4") (pintype "power_in"))
      (node (ref "U6") (pin "4") (pinfunction "V+_4") (pintype "power_in"))
      (node (ref "U7") (pin "4") (pinfunction "V+_4") (pintype "power_in"))
      (node (ref "U8") (pin "4") (pinfunction "V+_4") (pintype "power_in"))
      (node (ref "U9") (pin "4") (pinfunction "V+_4") (pintype "power_in"))
    )
    (net (code "3") (name "-18V") (class "Default")
      (node (ref "C53") (pin "2") (pinfunction "2_2") (pintype "passive"))
      (node (ref "C55") (pin "2") (pinfunction "2_2") (pintype "passive"))
      (node (ref "C57") (pin "2") (pinfunction "2_2") (pintype "passive"))
      (node (ref "C59") (pin "2") (pinfunction "2_2") (pintype "passive"))
      (node (ref "C61") (pin "2") (pinfunction "2_2") (pintype "passive"))
      (node (ref "C63") (pin "2") (pinfunction "2_2") (pintype "passive"))
      (node (ref "C65") (pin "2") (pinfunction "2_2") (pintype "passive"))
      (node (ref "C67") (pin "2") (pinfunction "2_2") (pintype "passive"))
      (node (ref "J1") (pin "11") (pinfunction "11_11") (pintype "passive"))
      (node (ref "U10") (pin "11") (pinfunction "V-_11") (pintype "power_in"))
      (node (ref "U11") (pin "11") (pinfunction "V-_11") (pintype "power_in"))
      (node (ref "U12") (pin "11") (pinfunction "V-_11") (pintype "power_in"))
      (node (ref "U13") (pin "11") (pinfunction "V-_11") (pintype "power_in"))
      (node (ref "U6") (pin "11") (pinfunction "V-_11") (pintype "power_in"))
      (node (ref "U7") (pin "11") (pinfunction "V-_11") (pintype "power_in"))
      (node (ref "U8") (pin "11") (pinfunction "V-_11") (pintype "power_in"))
      (node (ref "U9") (pin "11") (pinfunction "V-_11") (pintype "power_in"))
    )
    (net (code "4") (name "/ASEQ_Bass") (class "Default")
      (node (ref "C3") (pin "2") (pinfunction "2_2") (pintype "passive"))
      (node (ref "J1") (pin "12") (pinfunction "12_12") (pintype "passive"))
      (node (ref "R3") (pin "2") (pinfunction "2_2") (pintype "passive"))
      (node (ref "TP1") (pin "01") (pinfunction "01_01") (pintype "passive"))
    )
    (net (code "5") (name "/ASEQ_Höhen") (class "Default")
      (node (ref "C37") (pin "2") (pinfunction "2_2") (pintype "passive"))
      (node (ref "J1") (pin "10") (pinfunction "10_10") (pintype "passive"))
      (node (ref "R30") (pin "2") (pinfunction "2_2") (pintype "passive"))
      (node (ref "TP10") (pin "01") (pinfunction "01_01") (pintype "passive"))
    )
    (net (code "6") (name "/ASEQ_Kick") (class "Default")
      (node (ref "C14") (pin "2") (pinfunction "2_2") (pintype "passive"))
      (node (ref "J1") (pin "6") (pinfunction "6_6") (pintype "passive"))
      (node (ref "R9") (pin "2") (pinfunction "2_2") (pintype "passive"))
      (node (ref "TP4") (pin "01") (pinfunction "01_01") (pintype "passive"))
    )
    (net (code "7") (name "/ASEQ_Mitten") (class "Default")
      (node (ref "C25") (pin "2") (pinfunction "2_2") (pintype "passive"))
      (node (ref "J1") (pin "8") (pinfunction "8_8") (pintype "passive"))
      (node (ref "R19") (pin "2") (pinfunction "2_2") (pintype "passive"))
      (node (ref "TP7") (pin "01") (pinfunction "01_01") (pintype "passive"))
    )
    (net (code "8") (name "/AUX_Sum") (class "Default")
      (node (ref "J1") (pin "2") (pinfunction "2_2") (pintype "passive"))
      (node (ref "R16") (pin "1") (pinfunction "1_1") (pintype "passive"))
      (node (ref "R29") (pin "1") (pinfunction "1_1") (pintype "passive"))
      (node (ref "R42") (pin "1") (pinfunction "1_1") (pintype "passive"))
    )
    (net (code "9") (name "/Bass_In") (class "Default")
      (node (ref "C8") (pin "1") (pinfunction "1_1") (pintype "passive"))
      (node (ref "R2") (pin "2") (pinfunction "2_2") (pintype "passive"))
      (node (ref "TP2") (pin "01") (pinfunction "01_01") (pintype "passive"))
      (node (ref "U7") (pin "14") (pinfunction "OUT_D_14") (pintype "output"))
    )
    (net (code "10") (name "/Clock") (class "Default")
      (node (ref "MD1") (pin "16") (pinfunction "D13/SCK_16") (pintype "bidirectional"))
      (node (ref "U14") (pin "5") (pinfunction "SCK_5") (pintype "input"))
      (node (ref "U15") (pin "5") (pinfunction "SCK_5") (pintype "input"))
      (node (ref "U16") (pin "5") (pinfunction "SCK_5") (pintype "input"))
      (node (ref "U17") (pin "5") (pinfunction "SCK_5") (pintype "input"))
      (node (ref "U18") (pin "5") (pinfunction "SCK_5") (pintype "input"))
      (node (ref "U19") (pin "5") (pinfunction "SCK_5") (pintype "input"))
      (node (ref "U20") (pin "5") (pinfunction "SCK_5") (pintype "input"))
      (node (ref "U21") (pin "5") (pinfunction "SCK_5") (pintype "input"))
    )
    (net (code "11") (name "/DP_1") (class "Default")
      (node (ref "MD1") (pin "5") (pinfunction "D2_5") (pintype "bidirectional"))
      (node (ref "U14") (pin "4") (pinfunction "~{CS}_4") (pintype "input"))
    )
    (net (code "12") (name "/DP_1B") (class "Default")
      (node (ref "C8") (pin "2") (pinfunction "2_2") (pintype "passive"))
      (node (ref "C9") (pin "1") (pinfunction "1_1") (pintype "passive"))
      (node (ref "U15") (pin "13") (pinfunction "P0B_13") (pintype "passive"))
    )
    (net (code "13") (name "/DP_1W") (class "Default")
      (node (ref "C5") (pin "1") (pinfunction "1_1") (pintype "passive"))
      (node (ref "U15") (pin "11") (pinfunction "P0A_11") (pintype "passive"))
      (node (ref "U15") (pin "12") (pinfunction "P0W_12") (pintype "passive"))
      (node (ref "U6") (pin "8") (pinfunction "OUT_C_8") (pintype "output"))
      (node (ref "U6") (pin "9") (pinfunction "IN_C-_9") (pintype "input"))
    )
    (net (code "14") (name "/DP_2") (class "Default")
      (node (ref "MD1") (pin "6") (pinfunction "D3_6") (pintype "bidirectional"))
      (node (ref "U15") (pin "4") (pinfunction "~{CS}_4") (pintype "input"))
    )
    (net (code "15") (name "/DP_2A") (class "Default")
      (node (ref "C9") (pin "2") (pinfunction "2_2") (pintype "passive"))
      (node (ref "U15") (pin "20") (pinfunction "P2A_20") (pintype "passive"))
      (node (ref "U6") (pin "10") (pinfunction "IN_C+_10") (pintype "input"))
    )
    (net (code "16") (name "/DP_3") (class "Default")
      (node (ref "MD1") (pin "7") (pinfunction "D4_7") (pintype "bidirectional"))
      (node (ref "U16") (pin "4") (pinfunction "~{CS}_4") (pintype "input"))
    )
    (net (code "17") (name "/DP_3B") (class "Default")
      (node (ref "C5") (pin "2") (pinfunction "2_2") (pintype "passive"))
      (node (ref "C6") (pin "1") (pinfunction "1_1") (pintype "passive"))
      (node (ref "U14") (pin "18") (pinfunction "P2B_18") (pintype "passive"))
    )
    (net (code "18") (name "/DP_3W") (class "Default")
      (node (ref "C4") (pin "1") (pinfunction "1_1") (pintype "passive"))
      (node (ref "U14") (pin "19") (pinfunction "P2W_19") (pintype "passive"))
      (node (ref "U14") (pin "20") (pinfunction "P2A_20") (pintype "passive"))
      (node (ref "U6") (pin "13") (pinfunction "IN_D-_13") (pintype "input"))
      (node (ref "U6") (pin "14") (pinfunction "OUT_D_14") (pintype "output"))
    )
    (net (code "19") (name "/DP_4") (class "Default")
      (node (ref "MD1") (pin "8") (pinfunction "D5_8") (pintype "bidirectional"))
      (node (ref "U17") (pin "4") (pinfunction "~{CS}_4") (pintype "input"))
    )
    (net (code "20") (name "/DP_4A") (class "Default")
      (node (ref "C6") (pin "2") (pinfunction "2_2") (pintype "passive"))
      (node (ref "U14") (pin "11") (pinfunction "P0A_11") (pintype "passive"))
      (node (ref "U6") (pin "12") (pinfunction "IN_D+_12") (pintype "input"))
    )
    (net (code "21") (name "/DP_5") (class "Default")
      (node (ref "MD1") (pin "9") (pinfunction "D6_9") (pintype "bidirectional"))
      (node (ref "U18") (pin "4") (pinfunction "~{CS}_4") (pintype "input"))
    )
    (net (code "22") (name "/DP_5A") (class "Default")
      (node (ref "C7") (pin "2") (pinfunction "2_2") (pintype "passive"))
      (node (ref "R5") (pin "2") (pinfunction "2_2") (pintype "passive"))
      (node (ref "TP3") (pin "01") (pinfunction "01_01") (pintype "passive"))
      (node (ref "U14") (pin "1") (pinfunction "P3A_1") (pintype "passive"))
    )
    (net (code "23") (name "/DP_5W") (class "Default")
      (node (ref "C1") (pin "1") (pinfunction "1_1") (pintype "passive"))
      (node (ref "U14") (pin "2") (pinfunction "P3W_2") (pintype "passive"))
      (node (ref "U14") (pin "3") (pinfunction "P3B_3") (pintype "passive"))
      (node (ref "U14") (pin "8") (pinfunction "P1B_8") (pintype "passive"))
    )
    (net (code "24") (name "/DP_6") (class "Default")
      (node (ref "MD1") (pin "10") (pinfunction "D7_10") (pintype "bidirectional"))
      (node (ref "U19") (pin "4") (pinfunction "~{CS}_4") (pintype "input"))
    )
    (net (code "25") (name "/DP_6W") (class "Default")
      (node (ref "C11") (pin "2") (pinfunction "2_2") (pintype "passive"))
      (node (ref "U14") (pin "10") (pinfunction "P1A_10") (pintype "passive"))
      (node (ref "U14") (pin "9") (pinfunction "P1W_9") (pintype "passive"))
      (node (ref "U7") (pin "3") (pinfunction "IN_A+_3") (pintype "input"))
    )
    (net (code "26") (name "/DP_7") (class "Default")
      (node (ref "MD1") (pin "11") (pinfunction "D8_11") (pintype "bidirectional"))
      (node (ref "U20") (pin "4") (pinfunction "~{CS}_4") (pintype "input"))
    )
    (net (code "27") (name "/DP_7A") (class "Default")
      (node (ref "C1") (pin "2") (pinfunction "2_2") (pintype "passive"))
      (node (ref "U15") (pin "1") (pinfunction "P3A_1") (pintype "passive"))
      (node (ref "U7") (pin "1") (pinfunction "OUT_A_1") (pintype "output"))
      (node (ref "U7") (pin "2") (pinfunction "IN_A-_2") (pintype "input"))
    )
    (net (code "28") (name "/DP_7W") (class "Default")
      (node (ref "C2") (pin "1") (pinfunction "1_1") (pintype "passive"))
      (node (ref "U15") (pin "2") (pinfunction "P3W_2") (pintype "passive"))
      (node (ref "U15") (pin "3") (pinfunction "P3B_3") (pintype "passive"))
      (node (ref "U15") (pin "8") (pinfunction "P1B_8") (pintype "passive"))
    )
    (net (code "29") (name "/DP_8") (class "Default")
      (node (ref "MD1") (pin "12") (pinfunction "D9_12") (pintype "bidirectional"))
      (node (ref "U21") (pin "4") (pinfunction "~{CS}_4") (pintype "input"))
    )
    (net (code "30") (name "/DP_8W") (class "Default")
      (node (ref "C10") (pin "2") (pinfunction "2_2") (pintype "passive"))
      (node (ref "U15") (pin "10") (pinfunction "P1A_10") (pintype "passive"))
      (node (ref "U15") (pin "9") (pinfunction "P1W_9") (pintype "passive"))
      (node (ref "U7") (pin "5") (pinfunction "IN_B+_5") (pintype "input"))
    )
    (net (code "31") (name "/DP_9B") (class "Default")
      (node (ref "C19") (pin "2") (pinfunction "2_2") (pintype "passive"))
      (node (ref "C20") (pin "1") (pinfunction "1_1") (pintype "passive"))
      (node (ref "U17") (pin "13") (pinfunction "P0B_13") (pintype "passive"))
    )
    (net (code "32") (name "/DP_9W") (class "Default")
      (node (ref "C16") (pin "1") (pinfunction "1_1") (pintype "passive"))
      (node (ref "U17") (pin "11") (pinfunction "P0A_11") (pintype "passive"))
      (node (ref "U17") (pin "12") (pinfunction "P0W_12") (pintype "passive"))
      (node (ref "U8") (pin "8") (pinfunction "OUT_C_8") (pintype "output"))
      (node (ref "U8") (pin "9") (pinfunction "IN_C-_9") (pintype "input"))
    )
    (net (code "33") (name "/DP_10A") (class "Default")
      (node (ref "C20") (pin "2") (pinfunction "2_2") (pintype "passive"))
      (node (ref "U17") (pin "20") (pinfunction "P2A_20") (pintype "passive"))
      (node (ref "U8") (pin "10") (pinfunction "IN_C+_10") (pintype "input"))
    )
    (net (code "34") (name "/DP_11B") (class "Default")
      (node (ref "C16") (pin "2") (pinfunction "2_2") (pintype "passive"))
      (node (ref "C17") (pin "1") (pinfunction "1_1") (pintype "passive"))
      (node (ref "U16") (pin "18") (pinfunction "P2B_18") (pintype "passive"))
    )
    (net (code "35") (name "/DP_11W") (class "Default")
      (node (ref "C15") (pin "1") (pinfunction "1_1") (pintype "passive"))
      (node (ref "U16") (pin "19") (pinfunction "P2W_19") (pintype "passive"))
      (node (ref "U16") (pin "20") (pinfunction "P2A_20") (pintype "passive"))
      (node (ref "U8") (pin "13") (pinfunction "IN_D-_13") (pintype "input"))
      (node (ref "U8") (pin "14") (pinfunction "OUT_D_14") (pintype "output"))
    )
    (net (code "36") (name "/DP_12A") (class "Default")
      (node (ref "C17") (pin "2") (pinfunction "2_2") (pintype "passive"))
      (node (ref "U16") (pin "11") (pinfunction "P0A_11") (pintype "passive"))
      (node (ref "U8") (pin "12") (pinfunction "IN_D+_12") (pintype "input"))
    )
    (net (code "37") (name "/DP_13A") (class "Default")
      (node (ref "C18") (pin "2") (pinfunction "2_2") (pintype "passive"))
      (node (ref "R11") (pin "2") (pinfunction "2_2") (pintype "passive"))
      (node (ref "TP5") (pin "01") (pinfunction "01_01") (pintype "passive"))
      (node (ref "U16") (pin "1") (pinfunction "P3A_1") (pintype "passive"))
    )
    (net (code "38") (name "/DP_13W") (class "Default")
      (node (ref "C13") (pin "1") (pinfunction "1_1") (pintype "passive"))
      (node (ref "U16") (pin "2") (pinfunction "P3W_2") (pintype "passive"))
      (node (ref "U16") (pin "3") (pinfunction "P3B_3") (pintype "passive"))
      (node (ref "U16") (pin "8") (pinfunction "P1B_8") (pintype "passive"))
    )
    (net (code "39") (name "/DP_14W") (class "Default")
      (node (ref "C22") (pin "2") (pinfunction "2_2") (pintype "passive"))
      (node (ref "U16") (pin "10") (pinfunction "P1A_10") (pintype "passive"))
      (node (ref "U16") (pin "9") (pinfunction "P1W_9") (pintype "passive"))
      (node (ref "U9") (pin "3") (pinfunction "IN_A+_3") (pintype "input"))
    )
    (net (code "40") (name "/DP_15A") (class "Default")
      (node (ref "C13") (pin "2") (pinfunction "2_2") (pintype "passive"))
      (node (ref "U17") (pin "1") (pinfunction "P3A_1") (pintype "passive"))
      (node (ref "U9") (pin "1") (pinfunction "OUT_A_1") (pintype "output"))
      (node (ref "U9") (pin "2") (pinfunction "IN_A-_2") (pintype "input"))
    )
    (net (code "41") (name "/DP_15W") (class "Default")
      (node (ref "C12") (pin "1") (pinfunction "1_1") (pintype "passive"))
      (node (ref "U17") (pin "2") (pinfunction "P3W_2") (pintype "passive"))
      (node (ref "U17") (pin "3") (pinfunction "P3B_3") (pintype "passive"))
      (node (ref "U17") (pin "8") (pinfunction "P1B_8") (pintype "passive"))
    )
    (net (code "42") (name "/DP_16W") (class "Default")
      (node (ref "C21") (pin "2") (pinfunction "2_2") (pintype "passive"))
      (node (ref "U17") (pin "10") (pinfunction "P1A_10") (pintype "passive"))
      (node (ref "U17") (pin "9") (pinfunction "P1W_9") (pintype "passive"))
      (node (ref "U9") (pin "5") (pinfunction "IN_B+_5") (pintype "input"))
    )
    (net (code "43") (name "/DP_17B") (class "Default")
      (node (ref "C31") (pin "2") (pinfunction "2_2") (pintype "passive"))
      (node (ref "C32") (pin "1") (pinfunction "1_1") (pintype "passive"))
      (node (ref "U19") (pin "13") (pinfunction "P0B_13") (pintype "passive"))
    )
    (net (code "44") (name "/DP_17W") (class "Default")
      (node (ref "C28") (pin "1") (pinfunction "1_1") (pintype "passive"))
      (node (ref "U10") (pin "8") (pinfunction "OUT_C_8") (pintype "output"))
      (node (ref "U10") (pin "9") (pinfunction "IN_C-_9") (pintype "input"))
      (node (ref "U19") (pin "11") (pinfunction "P0A_11") (pintype "passive"))
      (node (ref "U19") (pin "12") (pinfunction "P0W_12") (pintype "passive"))
    )
    (net (code "45") (name "/DP_18A") (class "Default")
      (node (ref "C32") (pin "2") (pinfunction "2_2") (pintype "passive"))
      (node (ref "U10") (pin "10") (pinfunction "IN_C+_10") (pintype "input"))
      (node (ref "U19") (pin "20") (pinfunction "P2A_20") (pintype "passive"))
    )
    (net (code "46") (name "/DP_19B") (class "Default")
      (node (ref "C28") (pin "2") (pinfunction "2_2") (pintype "passive"))
      (node (ref "C29") (pin "1") (pinfunction "1_1") (pintype "passive"))
      (node (ref "U18") (pin "18") (pinfunction "P2B_18") (pintype "passive"))
    )
    (net (code "47") (name "/DP_19W") (class "Default")
      (node (ref "C27") (pin "1") (pinfunction "1_1") (pintype "passive"))
      (node (ref "U10") (pin "13") (pinfunction "IN_D-_13") (pintype "input"))
      (node (ref "U10") (pin "14") (pinfunction "OUT_D_14") (pintype "output"))
      (node (ref "U18") (pin "19") (pinfunction "P2W_19") (pintype "passive"))
      (node (ref "U18") (pin "20") (pinfunction "P2A_20") (pintype "passive"))
    )
    (net (code "48") (name "/DP_20A") (class "Default")
      (node (ref "C29") (pin "2") (pinfunction "2_2") (pintype "passive"))
      (node (ref "U10") (pin "12") (pinfunction "IN_D+_12") (pintype "input"))
      (node (ref "U18") (pin "11") (pinfunction "P0A_11") (pintype "passive"))
    )
    (net (code "49") (name "/DP_21A") (class "Default")
      (node (ref "C30") (pin "2") (pinfunction "2_2") (pintype "passive"))
      (node (ref "R22") (pin "2") (pinfunction "2_2") (pintype "passive"))
      (node (ref "TP9") (pin "01") (pinfunction "01_01") (pintype "passive"))
      (node (ref "U18") (pin "1") (pinfunction "P3A_1") (pintype "passive"))
    )
    (net (code "50") (name "/DP_21W") (class "Default")
      (node (ref "C24") (pin "1") (pinfunction "1_1") (pintype "passive"))
      (node (ref "U18") (pin "2") (pinfunction "P3W_2") (pintype "passive"))
      (node (ref "U18") (pin "3") (pinfunction "P3B_3") (pintype "passive"))
      (node (ref "U18") (pin "8") (pinfunction "P1B_8") (pintype "passive"))
    )
    (net (code "51") (name "/DP_22W") (class "Default")
      (node (ref "C34") (pin "2") (pinfunction "2_2") (pintype "passive"))
      (node (ref "U11") (pin "3") (pinfunction "IN_A+_3") (pintype "input"))
      (node (ref "U18") (pin "10") (pinfunction "P1A_10") (pintype "passive"))
      (node (ref "U18") (pin "9") (pinfunction "P1W_9") (pintype "passive"))
    )
    (net (code "52") (name "/DP_23A") (class "Default")
      (node (ref "C24") (pin "2") (pinfunction "2_2") (pintype "passive"))
      (node (ref "U11") (pin "1") (pinfunction "OUT_A_1") (pintype "output"))
      (node (ref "U11") (pin "2") (pinfunction "IN_A-_2") (pintype "input"))
      (node (ref "U19") (pin "1") (pinfunction "P3A_1") (pintype "passive"))
    )
    (net (code "53") (name "/DP_23W") (class "Default")
      (node (ref "C23") (pin "1") (pinfunction "1_1") (pintype "passive"))
      (node (ref "U19") (pin "2") (pinfunction "P3W_2") (pintype "passive"))
      (node (ref "U19") (pin "3") (pinfunction "P3B_3") (pintype "passive"))
      (node (ref "U19") (pin "8") (pinfunction "P1B_8") (pintype "passive"))
    )
    (net (code "54") (name "/DP_24W") (class "Default")
      (node (ref "C33") (pin "2") (pinfunction "2_2") (pintype "passive"))
      (node (ref "U11") (pin "5") (pinfunction "IN_B+_5") (pintype "input"))
      (node (ref "U19") (pin "10") (pinfunction "P1A_10") (pintype "passive"))
      (node (ref "U19") (pin "9") (pinfunction "P1W_9") (pintype "passive"))
    )
    (net (code "55") (name "/DP_25B") (class "Default")
      (node (ref "C42") (pin "2") (pinfunction "2_2") (pintype "passive"))
      (node (ref "C43") (pin "1") (pinfunction "1_1") (pintype "passive"))
      (node (ref "U21") (pin "13") (pinfunction "P0B_13") (pintype "passive"))
    )
    (net (code "56") (name "/DP_25W") (class "Default")
      (node (ref "C39") (pin "1") (pinfunction "1_1") (pintype "passive"))
      (node (ref "U12") (pin "8") (pinfunction "OUT_C_8") (pintype "output"))
      (node (ref "U12") (pin "9") (pinfunction "IN_C-_9") (pintype "input"))
      (node (ref "U21") (pin "11") (pinfunction "P0A_11") (pintype "passive"))
      (node (ref "U21") (pin "12") (pinfunction "P0W_12") (pintype "passive"))
    )
    (net (code "57") (name "/DP_26A") (class "Default")
      (node (ref "C43") (pin "2") (pinfunction "2_2") (pintype "passive"))
      (node (ref "U12") (pin "10") (pinfunction "IN_C+_10") (pintype "input"))
      (node (ref "U21") (pin "20") (pinfunction "P2A_20") (pintype "passive"))
    )
    (net (code "58") (name "/DP_27B") (class "Default")
      (node (ref "C39") (pin "2") (pinfunction "2_2") (pintype "passive"))
      (node (ref "C40") (pin "1") (pinfunction "1_1") (pintype "passive"))
      (node (ref "U20") (pin "18") (pinfunction "P2B_18") (pintype "passive"))
    )
    (net (code "59") (name "/DP_27W") (class "Default")
      (node (ref "C38") (pin "1") (pinfunction "1_1") (pintype "passive"))
      (node (ref "U12") (pin "13") (pinfunction "IN_D-_13") (pintype "input"))
      (node (ref "U12") (pin "14") (pinfunction "OUT_D_14") (pintype "output"))
      (node (ref "U20") (pin "19") (pinfunction "P2W_19") (pintype "passive"))
      (node (ref "U20") (pin "20") (pinfunction "P2A_20") (pintype "passive"))
    )
    (net (code "60") (name "/DP_28A") (class "Default")
      (node (ref "C40") (pin "2") (pinfunction "2_2") (pintype "passive"))
      (node (ref "U12") (pin "12") (pinfunction "IN_D+_12") (pintype "input"))
      (node (ref "U20") (pin "11") (pinfunction "P0A_11") (pintype "passive"))
    )
    (net (code "61") (name "/DP_29A") (class "Default")
      (node (ref "C41") (pin "2") (pinfunction "2_2") (pintype "passive"))
      (node (ref "R32") (pin "2") (pinfunction "2_2") (pintype "passive"))
      (node (ref "TP12") (pin "01") (pinfunction "01_01") (pintype "passive"))
      (node (ref "U20") (pin "1") (pinfunction "P3A_1") (pintype "passive"))
    )
    (net (code "62") (name "/DP_29W") (class "Default")
      (node (ref "C36") (pin "1") (pinfunction "1_1") (pintype "passive"))
      (node (ref "U20") (pin "2") (pinfunction "P3W_2") (pintype "passive"))
      (node (ref "U20") (pin "3") (pinfunction "P3B_3") (pintype "passive"))
      (node (ref "U20") (pin "8") (pinfunction "P1B_8") (pintype "passive"))
    )
    (net (code "63") (name "/DP_30W") (class "Default")
      (node (ref "C46") (pin "2") (pinfunction "2_2") (pintype "passive"))
      (node (ref "U13") (pin "3") (pinfunction "IN_A+_3") (pintype "input"))
      (node (ref "U20") (pin "10") (pinfunction "P1A_10") (pintype "passive"))
      (node (ref "U20") (pin "9") (pinfunction "P1W_9") (pintype "passive"))
    )
    (net (code "64") (name "/DP_31A") (class "Default")
      (node (ref "C36") (pin "2") (pinfunction "2_2") (pintype "passive"))
      (node (ref "U13") (pin "1") (pinfunction "OUT_A_1") (pintype "output"))
      (node (ref "U13") (pin "2") (pinfunction "IN_A-_2") (pintype "input"))
      (node (ref "U21") (pin "1") (pinfunction "P3A_1") (pintype "passive"))
    )
    (net (code "65") (name "/DP_31W") (class "Default")
      (node (ref "C35") (pin "1") (pinfunction "1_1") (pintype "passive"))
      (node (ref "U21") (pin "2") (pinfunction "P3W_2") (pintype "passive"))
      (node (ref "U21") (pin "3") (pinfunction "P3B_3") (pintype "passive"))
      (node (ref "U21") (pin "8") (pinfunction "P1B_8") (pintype "passive"))
    )
    (net (code "66") (name "/DP_32W") (class "Default")
      (node (ref "C44") (pin "2") (pinfunction "2_2") (pintype "passive"))
      (node (ref "U13") (pin "5") (pinfunction "IN_B+_5") (pintype "input"))
      (node (ref "U21") (pin "10") (pinfunction "P1A_10") (pintype "passive"))
      (node (ref "U21") (pin "9") (pinfunction "P1W_9") (pintype "passive"))
    )
    (net (code "67") (name "/Data") (class "Default")
      (node (ref "MD1") (pin "15") (pinfunction "D12/MISO_15") (pintype "bidirectional"))
      (node (ref "U14") (pin "6") (pinfunction "SDI_6") (pintype "input"))
      (node (ref "U15") (pin "6") (pinfunction "SDI_6") (pintype "input"))
      (node (ref "U16") (pin "6") (pinfunction "SDI_6") (pintype "input"))
      (node (ref "U17") (pin "6") (pinfunction "SDI_6") (pintype "input"))
      (node (ref "U18") (pin "6") (pinfunction "SDI_6") (pintype "input"))
      (node (ref "U19") (pin "6") (pinfunction "SDI_6") (pintype "input"))
      (node (ref "U20") (pin "6") (pinfunction "SDI_6") (pintype "input"))
      (node (ref "U21") (pin "6") (pinfunction "SDI_6") (pintype "input"))
    )
    (net (code "68") (name "/Höhen_In") (class "Default")
      (node (ref "C42") (pin "1") (pinfunction "1_1") (pintype "passive"))
      (node (ref "R40") (pin "2") (pinfunction "2_2") (pintype "passive"))
      (node (ref "TP11") (pin "01") (pinfunction "01_01") (pintype "passive"))
      (node (ref "U12") (pin "7") (pinfunction "OUT_B_7") (pintype "output"))
    )
    (net (code "69") (name "/KST_1_1 {slash} Line_Aux") (class "Default")
      (node (ref "J1") (pin "4") (pinfunction "4_4") (pintype "passive"))
      (node (ref "U11") (pin "10") (pinfunction "IN_C+_10") (pintype "input"))
      (node (ref "U13") (pin "10") (pinfunction "IN_C+_10") (pintype "input"))
      (node (ref "U7") (pin "10") (pinfunction "IN_C+_10") (pintype "input"))
      (node (ref "U9") (pin "10") (pinfunction "IN_C+_10") (pintype "input"))
    )
    (net (code "70") (name "/KST_1_2") (class "Default")
      (node (ref "J1") (pin "1") (pinfunction "1_1") (pintype "passive"))
      (node (ref "R15") (pin "1") (pinfunction "1_1") (pintype "passive"))
      (node (ref "R28") (pin "1") (pinfunction "1_1") (pintype "passive"))
      (node (ref "R41") (pin "1") (pinfunction "1_1") (pintype "passive"))
    )
    (net (code "71") (name "/Kick_In") (class "Default")
      (node (ref "C19") (pin "1") (pinfunction "1_1") (pintype "passive"))
      (node (ref "R14") (pin "2") (pinfunction "2_2") (pintype "passive"))
      (node (ref "TP6") (pin "01") (pinfunction "01_01") (pintype "passive"))
      (node (ref "U8") (pin "7") (pinfunction "OUT_B_7") (pintype "output"))
    )
    (net (code "72") (name "/Mitten_In") (class "Default")
      (node (ref "C31") (pin "1") (pinfunction "1_1") (pintype "passive"))
      (node (ref "R27") (pin "2") (pinfunction "2_2") (pintype "passive"))
      (node (ref "TP8") (pin "01") (pinfunction "01_01") (pintype "passive"))
      (node (ref "U10") (pin "7") (pinfunction "OUT_B_7") (pintype "output"))
    )
    (net (code "73") (name "/Reset") (class "Default")
      (node (ref "MD1") (pin "3") (pinfunction "~{RESET}_3") (pintype "passive"))
      (node (ref "U14") (pin "15") (pinfunction "~{RESET}_15") (pintype "input"))
      (node (ref "U15") (pin "15") (pinfunction "~{RESET}_15") (pintype "input"))
      (node (ref "U16") (pin "15") (pinfunction "~{RESET}_15") (pintype "input"))
      (node (ref "U17") (pin "15") (pinfunction "~{RESET}_15") (pintype "input"))
      (node (ref "U18") (pin "15") (pinfunction "~{RESET}_15") (pintype "input"))
      (node (ref "U19") (pin "15") (pinfunction "~{RESET}_15") (pintype "input"))
      (node (ref "U20") (pin "15") (pinfunction "~{RESET}_15") (pintype "input"))
      (node (ref "U21") (pin "15") (pinfunction "~{RESET}_15") (pintype "input"))
    )
    (net (code "74") (name "5V_DP") (class "Default")
      (node (ref "C48") (pin "2") (pinfunction "2_2") (pintype "passive"))
      (node (ref "C49") (pin "2") (pinfunction "2_2") (pintype "passive"))
      (node (ref "C50") (pin "2") (pinfunction "2_2") (pintype "passive"))
      (node (ref "C51") (pin "2") (pinfunction "2_2") (pintype "passive"))
      (node (ref "C69") (pin "2") (pinfunction "2_2") (pintype "passive"))
      (node (ref "C70") (pin "2") (pinfunction "2_2") (pintype "passive"))
      (node (ref "C71") (pin "2") (pinfunction "2_2") (pintype "passive"))
      (node (ref "C72") (pin "2") (pinfunction "2_2") (pintype "passive"))
      (node (ref "MD1") (pin "27") (pinfunction "+5V_27") (pintype "power_in"))
      (node (ref "U14") (pin "17") (pinfunction "VDD_17") (pintype "power_in"))
      (node (ref "U15") (pin "17") (pinfunction "VDD_17") (pintype "power_in"))
      (node (ref "U16") (pin "17") (pinfunction "VDD_17") (pintype "power_in"))
      (node (ref "U17") (pin "17") (pinfunction "VDD_17") (pintype "power_in"))
      (node (ref "U18") (pin "17") (pinfunction "VDD_17") (pintype "power_in"))
      (node (ref "U19") (pin "17") (pinfunction "VDD_17") (pintype "power_in"))
      (node (ref "U20") (pin "17") (pinfunction "VDD_17") (pintype "power_in"))
      (node (ref "U21") (pin "17") (pinfunction "VDD_17") (pintype "power_in"))
    )
    (net (code "75") (name "Masse") (class "Default")
      (node (ref "C10") (pin "1") (pinfunction "1_1") (pintype "passive"))
      (node (ref "C11") (pin "1") (pinfunction "1_1") (pintype "passive"))
      (node (ref "C21") (pin "1") (pinfunction "1_1") (pintype "passive"))
      (node (ref "C22") (pin "1") (pinfunction "1_1") (pintype "passive"))
      (node (ref "C33") (pin "1") (pinfunction "1_1") (pintype "passive"))
      (node (ref "C34") (pin "1") (pinfunction "1_1") (pintype "passive"))
      (node (ref "C44") (pin "1") (pinfunction "1_1") (pintype "passive"))
      (node (ref "C46") (pin "1") (pinfunction "1_1") (pintype "passive"))
      (node (ref "C48") (pin "1") (pinfunction "1_1") (pintype "passive"))
      (node (ref "C49") (pin "1") (pinfunction "1_1") (pintype "passive"))
      (node (ref "C50") (pin "1") (pinfunction "1_1") (pintype "passive"))
      (node (ref "C51") (pin "1") (pinfunction "1_1") (pintype "passive"))
      (node (ref "C52") (pin "1") (pinfunction "1_1") (pintype "passive"))
      (node (ref "C53") (pin "1") (pinfunction "1_1") (pintype "passive"))
      (node (ref "C54") (pin "1") (pinfunction "1_1") (pintype "passive"))
      (node (ref "C55") (pin "1") (pinfunction "1_1") (pintype "passive"))
      (node (ref "C56") (pin "1") (pinfunction "1_1") (pintype "passive"))
      (node (ref "C57") (pin "1") (pinfunction "1_1") (pintype "passive"))
      (node (ref "C58") (pin "1") (pinfunction "1_1") (pintype "passive"))
      (node (ref "C59") (pin "1") (pinfunction "1_1") (pintype "passive"))
      (node (ref "C60") (pin "1") (pinfunction "1_1") (pintype "passive"))
      (node (ref "C61") (pin "1") (pinfunction "1_1") (pintype "passive"))
      (node (ref "C62") (pin "1") (pinfunction "1_1") (pintype "passive"))
      (node (ref "C63") (pin "1") (pinfunction "1_1") (pintype "passive"))
      (node (ref "C64") (pin "1") (pinfunction "1_1") (pintype "passive"))
      (node (ref "C65") (pin "1") (pinfunction "1_1") (pintype "passive"))
      (node (ref "C66") (pin "1") (pinfunction "1_1") (pintype "passive"))
      (node (ref "C67") (pin "1") (pinfunction "1_1") (pintype "passive"))
      (node (ref "C68") (pin "1") (pinfunction "1_1") (pintype "passive"))
      (node (ref "C69") (pin "1") (pinfunction "1_1") (pintype "passive"))
      (node (ref "C70") (pin "1") (pinfunction "1_1") (pintype "passive"))
      (node (ref "C71") (pin "1") (pinfunction "1_1") (pintype "passive"))
      (node (ref "C72") (pin "1") (pinfunction "1_1") (pintype "passive"))
      (node (ref "J1") (pin "3") (pinfunction "3_3") (pintype "passive"))
      (node (ref "J1") (pin "5") (pinfunction "5_5") (pintype "passive"))
      (node (ref "J1") (pin "9") (pinfunction "9_9") (pintype "passive"))
      (node (ref "MD1") (pin "29") (pinfunction "GND_29") (pintype "power_in"))
      (node (ref "MD1") (pin "4") (pinfunction "GND_4") (pintype "power_in"))
      (node (ref "R10") (pin "1") (pinfunction "1_1") (pintype "passive"))
      (node (ref "R11") (pin "1") (pinfunction "1_1") (pintype "passive"))
      (node (ref "R19") (pin "1") (pinfunction "1_1") (pintype "passive"))
      (node (ref "R20") (pin "1") (pinfunction "1_1") (pintype "passive"))
      (node (ref "R21") (pin "1") (pinfunction "1_1") (pintype "passive"))
      (node (ref "R22") (pin "1") (pinfunction "1_1") (pintype "passive"))
      (node (ref "R24") (pin "1") (pinfunction "1_1") (pintype "passive"))
      (node (ref "R3") (pin "1") (pinfunction "1_1") (pintype "passive"))
      (node (ref "R30") (pin "1") (pinfunction "1_1") (pintype "passive"))
      (node (ref "R31") (pin "1") (pinfunction "1_1") (pintype "passive"))
      (node (ref "R32") (pin "1") (pinfunction "1_1") (pintype "passive"))
      (node (ref "R35") (pin "1") (pinfunction "1_1") (pintype "passive"))
      (node (ref "R37") (pin "1") (pinfunction "1_1") (pintype "passive"))
      (node (ref "R4") (pin "1") (pinfunction "1_1") (pintype "passive"))
      (node (ref "R45") (pin "1") (pinfunction "1_1") (pintype "passive"))
      (node (ref "R47") (pin "1") (pinfunction "1_1") (pintype "passive"))
      (node (ref "R5") (pin "1") (pinfunction "1_1") (pintype "passive"))
      (node (ref "R8") (pin "1") (pinfunction "1_1") (pintype "passive"))
      (node (ref "R9") (pin "1") (pinfunction "1_1") (pintype "passive"))
      (node (ref "U10") (pin "5") (pinfunction "IN_B+_5") (pintype "input"))
      (node (ref "U12") (pin "5") (pinfunction "IN_B+_5") (pintype "input"))
      (node (ref "U14") (pin "12") (pinfunction "P0W_12") (pintype "passive"))
      (node (ref "U14") (pin "13") (pinfunction "P0B_13") (pintype "passive"))
      (node (ref "U14") (pin "7") (pinfunction "VSS_7") (pintype "power_in"))
      (node (ref "U15") (pin "18") (pinfunction "P2B_18") (pintype "passive"))
      (node (ref "U15") (pin "19") (pinfunction "P2W_19") (pintype "passive"))
      (node (ref "U15") (pin "7") (pinfunction "VSS_7") (pintype "power_in"))
      (node (ref "U16") (pin "12") (pinfunction "P0W_12") (pintype "passive"))
      (node (ref "U16") (pin "13") (pinfunction "P0B_13") (pintype "passive"))
      (node (ref "U16") (pin "7") (pinfunction "VSS_7") (pintype "power_in"))
      (node (ref "U17") (pin "18") (pinfunction "P2B_18") (pintype "passive"))
      (node (ref "U17") (pin "19") (pinfunction "P2W_19") (pintype "passive"))
      (node (ref "U17") (pin "7") (pinfunction "VSS_7") (pintype "power_in"))
      (node (ref "U18") (pin "12") (pinfunction "P0W_12") (pintype "passive"))
      (node (ref "U18") (pin "13") (pinfunction "P0B_13") (pintype "passive"))
      (node (ref "U18") (pin "7") (pinfunction "VSS_7") (pintype "power_in"))
      (node (ref "U19") (pin "18") (pinfunction "P2B_18") (pintype "passive"))
      (node (ref "U19") (pin "19") (pinfunction "P2W_19") (pintype "passive"))
      (node (ref "U19") (pin "7") (pinfunction "VSS_7") (pintype "power_in"))
      (node (ref "U20") (pin "12") (pinfunction "P0W_12") (pintype "passive"))
      (node (ref "U20") (pin "13") (pinfunction "P0B_13") (pintype "passive"))
      (node (ref "U20") (pin "7") (pinfunction "VSS_7") (pintype "power_in"))
      (node (ref "U21") (pin "18") (pinfunction "P2B_18") (pintype "passive"))
      (node (ref "U21") (pin "19") (pinfunction "P2W_19") (pintype "passive"))
      (node (ref "U21") (pin "7") (pinfunction "VSS_7") (pintype "power_in"))
      (node (ref "U6") (pin "5") (pinfunction "IN_B+_5") (pintype "input"))
      (node (ref "U8") (pin "5") (pinfunction "IN_B+_5") (pintype "input"))
    )
    (net (code "76") (name "Net-(C26-Pad2)") (class "Default")
      (node (ref "C26") (pin "2") (pinfunction "2_2") (pintype "passive"))
      (node (ref "R17") (pin "1") (pinfunction "1_1") (pintype "passive"))
      (node (ref "R20") (pin "2") (pinfunction "2_2") (pintype "passive"))
    )
    (net (code "77") (name "Net-(C45-Pad2)") (class "Default")
      (node (ref "C45") (pin "2") (pinfunction "2_2") (pintype "passive"))
      (node (ref "R33") (pin "1") (pinfunction "1_1") (pintype "passive"))
      (node (ref "R35") (pin "2") (pinfunction "2_2") (pintype "passive"))
    )
    (net (code "78") (name "Net-(C47-Pad2)") (class "Default")
      (node (ref "C47") (pin "2") (pinfunction "2_2") (pintype "passive"))
      (node (ref "R43") (pin "1") (pinfunction "1_1") (pintype "passive"))
      (node (ref "R45") (pin "2") (pinfunction "2_2") (pintype "passive"))
    )
    (net (code "79") (name "Net-(U6A-IN_A+)") (class "Default")
      (node (ref "C4") (pin "2") (pinfunction "2_2") (pintype "passive"))
      (node (ref "R4") (pin "2") (pinfunction "2_2") (pintype "passive"))
      (node (ref "U6") (pin "3") (pinfunction "IN_A+_3") (pintype "input"))
    )
    (net (code "80") (name "Net-(U6A-IN_A-)") (class "Default")
      (node (ref "C7") (pin "1") (pinfunction "1_1") (pintype "passive"))
      (node (ref "U6") (pin "1") (pinfunction "OUT_A_1") (pintype "output"))
      (node (ref "U6") (pin "2") (pinfunction "IN_A-_2") (pintype "input"))
    )
    (net (code "81") (name "Net-(U6B-IN_B-)") (class "Default")
      (node (ref "U6") (pin "6") (pinfunction "IN_B-_6") (pintype "input"))
      (node (ref "U6") (pin "7") (pinfunction "OUT_B_7") (pintype "output"))
    )
    (net (code "82") (name "Net-(U7B-IN_B-)") (class "Default")
      (node (ref "C2") (pin "2") (pinfunction "2_2") (pintype "passive"))
      (node (ref "C3") (pin "1") (pinfunction "1_1") (pintype "passive"))
      (node (ref "U7") (pin "6") (pinfunction "IN_B-_6") (pintype "input"))
      (node (ref "U7") (pin "7") (pinfunction "OUT_B_7") (pintype "output"))
    )
    (net (code "83") (name "Net-(U7C-IN_C-)") (class "Default")
      (node (ref "R6") (pin "2") (pinfunction "2_2") (pintype "passive"))
      (node (ref "R6") (pin "3") (pinfunction "3_3") (pintype "passive"))
      (node (ref "R7") (pin "1") (pinfunction "1_1") (pintype "passive"))
      (node (ref "S1") (pin "2") (pinfunction "2_2") (pintype "passive"))
      (node (ref "U7") (pin "9") (pinfunction "IN_C-_9") (pintype "input"))
    )
    (net (code "84") (name "Net-(U7C-OUT_C)") (class "Default")
      (node (ref "R1") (pin "1") (pinfunction "1_1") (pintype "passive"))
      (node (ref "R6") (pin "1") (pinfunction "1_1") (pintype "passive"))
      (node (ref "S1") (pin "3") (pinfunction "3_3") (pintype "passive"))
      (node (ref "U7") (pin "8") (pinfunction "OUT_C_8") (pintype "output"))
    )
    (net (code "85") (name "Net-(U7D-IN_D+)") (class "Default")
      (node (ref "R7") (pin "2") (pinfunction "2_2") (pintype "passive"))
      (node (ref "R8") (pin "2") (pinfunction "2_2") (pintype "passive"))
      (node (ref "U7") (pin "12") (pinfunction "IN_D+_12") (pintype "input"))
    )
    (net (code "86") (name "Net-(U7D-IN_D-)") (class "Default")
      (node (ref "R1") (pin "2") (pinfunction "2_2") (pintype "passive"))
      (node (ref "R2") (pin "1") (pinfunction "1_1") (pintype "passive"))
      (node (ref "U7") (pin "13") (pinfunction "IN_D-_13") (pintype "input"))
    )
    (net (code "87") (name "Net-(U8A-IN_A+)") (class "Default")
      (node (ref "C15") (pin "2") (pinfunction "2_2") (pintype "passive"))
      (node (ref "R10") (pin "2") (pinfunction "2_2") (pintype "passive"))
      (node (ref "U8") (pin "3") (pinfunction "IN_A+_3") (pintype "input"))
    )
    (net (code "88") (name "Net-(U8A-IN_A-)") (class "Default")
      (node (ref "C18") (pin "1") (pinfunction "1_1") (pintype "passive"))
      (node (ref "U8") (pin "1") (pinfunction "OUT_A_1") (pintype "output"))
      (node (ref "U8") (pin "2") (pinfunction "IN_A-_2") (pintype "input"))
    )
    (net (code "89") (name "Net-(U8B-IN_B-)") (class "Default")
      (node (ref "R14") (pin "1") (pinfunction "1_1") (pintype "passive"))
      (node (ref "R15") (pin "2") (pinfunction "2_2") (pintype "passive"))
      (node (ref "R16") (pin "2") (pinfunction "2_2") (pintype "passive"))
      (node (ref "R17") (pin "2") (pinfunction "2_2") (pintype "passive"))
      (node (ref "U8") (pin "6") (pinfunction "IN_B-_6") (pintype "input"))
    )
    (net (code "90") (name "Net-(U9B-IN_B-)") (class "Default")
      (node (ref "C12") (pin "2") (pinfunction "2_2") (pintype "passive"))
      (node (ref "C14") (pin "1") (pinfunction "1_1") (pintype "passive"))
      (node (ref "U9") (pin "6") (pinfunction "IN_B-_6") (pintype "input"))
      (node (ref "U9") (pin "7") (pinfunction "OUT_B_7") (pintype "output"))
    )
    (net (code "91") (name "Net-(U9C-IN_C-)") (class "Default")
      (node (ref "R18") (pin "2") (pinfunction "2_2") (pintype "passive"))
      (node (ref "R18") (pin "3") (pinfunction "3_3") (pintype "passive"))
      (node (ref "R23") (pin "1") (pinfunction "1_1") (pintype "passive"))
      (node (ref "S2") (pin "2") (pinfunction "2_2") (pintype "passive"))
      (node (ref "U9") (pin "9") (pinfunction "IN_C-_9") (pintype "input"))
    )
    (net (code "92") (name "Net-(U9C-OUT_C)") (class "Default")
      (node (ref "R12") (pin "1") (pinfunction "1_1") (pintype "passive"))
      (node (ref "R18") (pin "1") (pinfunction "1_1") (pintype "passive"))
      (node (ref "S2") (pin "3") (pinfunction "3_3") (pintype "passive"))
      (node (ref "U9") (pin "8") (pinfunction "OUT_C_8") (pintype "output"))
    )
    (net (code "93") (name "Net-(U9D-IN_D+)") (class "Default")
      (node (ref "R23") (pin "2") (pinfunction "2_2") (pintype "passive"))
      (node (ref "R24") (pin "2") (pinfunction "2_2") (pintype "passive"))
      (node (ref "U9") (pin "12") (pinfunction "IN_D+_12") (pintype "input"))
    )
    (net (code "94") (name "Net-(U9D-IN_D-)") (class "Default")
      (node (ref "R12") (pin "2") (pinfunction "2_2") (pintype "passive"))
      (node (ref "R13") (pin "1") (pinfunction "1_1") (pintype "passive"))
      (node (ref "U9") (pin "13") (pinfunction "IN_D-_13") (pintype "input"))
    )
    (net (code "95") (name "Net-(U9D-OUT_D)") (class "Default")
      (node (ref "C26") (pin "1") (pinfunction "1_1") (pintype "passive"))
      (node (ref "R13") (pin "2") (pinfunction "2_2") (pintype "passive"))
      (node (ref "U9") (pin "14") (pinfunction "OUT_D_14") (pintype "output"))
    )
    (net (code "96") (name "Net-(U10A-IN_A+)") (class "Default")
      (node (ref "C27") (pin "2") (pinfunction "2_2") (pintype "passive"))
      (node (ref "R21") (pin "2") (pinfunction "2_2") (pintype "passive"))
      (node (ref "U10") (pin "3") (pinfunction "IN_A+_3") (pintype "input"))
    )
    (net (code "97") (name "Net-(U10A-IN_A-)") (class "Default")
      (node (ref "C30") (pin "1") (pinfunction "1_1") (pintype "passive"))
      (node (ref "U10") (pin "1") (pinfunction "OUT_A_1") (pintype "output"))
      (node (ref "U10") (pin "2") (pinfunction "IN_A-_2") (pintype "input"))
    )
    (net (code "98") (name "Net-(U10B-IN_B-)") (class "Default")
      (node (ref "R27") (pin "1") (pinfunction "1_1") (pintype "passive"))
      (node (ref "R28") (pin "2") (pinfunction "2_2") (pintype "passive"))
      (node (ref "R29") (pin "2") (pinfunction "2_2") (pintype "passive"))
      (node (ref "R33") (pin "2") (pinfunction "2_2") (pintype "passive"))
      (node (ref "U10") (pin "6") (pinfunction "IN_B-_6") (pintype "input"))
    )
    (net (code "99") (name "Net-(U11B-IN_B-)") (class "Default")
      (node (ref "C23") (pin "2") (pinfunction "2_2") (pintype "passive"))
      (node (ref "C25") (pin "1") (pinfunction "1_1") (pintype "passive"))
      (node (ref "U11") (pin "6") (pinfunction "IN_B-_6") (pintype "input"))
      (node (ref "U11") (pin "7") (pinfunction "OUT_B_7") (pintype "output"))
    )
    (net (code "100") (name "Net-(U11C-IN_C-)") (class "Default")
      (node (ref "R34") (pin "2") (pinfunction "2_2") (pintype "passive"))
      (node (ref "R34") (pin "3") (pinfunction "3_3") (pintype "passive"))
      (node (ref "R36") (pin "1") (pinfunction "1_1") (pintype "passive"))
      (node (ref "S3") (pin "2") (pinfunction "2_2") (pintype "passive"))
      (node (ref "U11") (pin "9") (pinfunction "IN_C-_9") (pintype "input"))
    )
    (net (code "101") (name "Net-(U11C-OUT_C)") (class "Default")
      (node (ref "R25") (pin "1") (pinfunction "1_1") (pintype "passive"))
      (node (ref "R34") (pin "1") (pinfunction "1_1") (pintype "passive"))
      (node (ref "S3") (pin "3") (pinfunction "3_3") (pintype "passive"))
      (node (ref "U11") (pin "8") (pinfunction "OUT_C_8") (pintype "output"))
    )
    (net (code "102") (name "Net-(U11D-IN_D+)") (class "Default")
      (node (ref "R36") (pin "2") (pinfunction "2_2") (pintype "passive"))
      (node (ref "R37") (pin "2") (pinfunction "2_2") (pintype "passive"))
      (node (ref "U11") (pin "12") (pinfunction "IN_D+_12") (pintype "input"))
    )
    (net (code "103") (name "Net-(U11D-IN_D-)") (class "Default")
      (node (ref "R25") (pin "2") (pinfunction "2_2") (pintype "passive"))
      (node (ref "R26") (pin "1") (pinfunction "1_1") (pintype "passive"))
      (node (ref "U11") (pin "13") (pinfunction "IN_D-_13") (pintype "input"))
    )
    (net (code "104") (name "Net-(U11D-OUT_D)") (class "Default")
      (node (ref "C45") (pin "1") (pinfunction "1_1") (pintype "passive"))
      (node (ref "R26") (pin "2") (pinfunction "2_2") (pintype "passive"))
      (node (ref "U11") (pin "14") (pinfunction "OUT_D_14") (pintype "output"))
    )
    (net (code "105") (name "Net-(U12A-IN_A+)") (class "Default")
      (node (ref "C38") (pin "2") (pinfunction "2_2") (pintype "passive"))
      (node (ref "R31") (pin "2") (pinfunction "2_2") (pintype "passive"))
      (node (ref "U12") (pin "3") (pinfunction "IN_A+_3") (pintype "input"))
    )
    (net (code "106") (name "Net-(U12A-IN_A-)") (class "Default")
      (node (ref "C41") (pin "1") (pinfunction "1_1") (pintype "passive"))
      (node (ref "U12") (pin "1") (pinfunction "OUT_A_1") (pintype "output"))
      (node (ref "U12") (pin "2") (pinfunction "IN_A-_2") (pintype "input"))
    )
    (net (code "107") (name "Net-(U12B-IN_B-)") (class "Default")
      (node (ref "R40") (pin "1") (pinfunction "1_1") (pintype "passive"))
      (node (ref "R41") (pin "2") (pinfunction "2_2") (pintype "passive"))
      (node (ref "R42") (pin "2") (pinfunction "2_2") (pintype "passive"))
      (node (ref "R43") (pin "2") (pinfunction "2_2") (pintype "passive"))
      (node (ref "U12") (pin "6") (pinfunction "IN_B-_6") (pintype "input"))
    )
    (net (code "108") (name "Net-(U13B-IN_B-)") (class "Default")
      (node (ref "C35") (pin "2") (pinfunction "2_2") (pintype "passive"))
      (node (ref "C37") (pin "1") (pinfunction "1_1") (pintype "passive"))
      (node (ref "U13") (pin "6") (pinfunction "IN_B-_6") (pintype "input"))
      (node (ref "U13") (pin "7") (pinfunction "OUT_B_7") (pintype "output"))
    )
    (net (code "109") (name "Net-(U13C-IN_C-)") (class "Default")
      (node (ref "R44") (pin "2") (pinfunction "2_2") (pintype "passive"))
      (node (ref "R44") (pin "3") (pinfunction "3_3") (pintype "passive"))
      (node (ref "R46") (pin "1") (pinfunction "1_1") (pintype "passive"))
      (node (ref "S4") (pin "2") (pinfunction "2_2") (pintype "passive"))
      (node (ref "U13") (pin "9") (pinfunction "IN_C-_9") (pintype "input"))
    )
    (net (code "110") (name "Net-(U13C-OUT_C)") (class "Default")
      (node (ref "R38") (pin "1") (pinfunction "1_1") (pintype "passive"))
      (node (ref "R44") (pin "1") (pinfunction "1_1") (pintype "passive"))
      (node (ref "S4") (pin "3") (pinfunction "3_3") (pintype "passive"))
      (node (ref "U13") (pin "8") (pinfunction "OUT_C_8") (pintype "output"))
    )
    (net (code "111") (name "Net-(U13D-IN_D+)") (class "Default")
      (node (ref "R46") (pin "2") (pinfunction "2_2") (pintype "passive"))
      (node (ref "R47") (pin "2") (pinfunction "2_2") (pintype "passive"))
      (node (ref "U13") (pin "12") (pinfunction "IN_D+_12") (pintype "input"))
    )
    (net (code "112") (name "Net-(U13D-IN_D-)") (class "Default")
      (node (ref "R38") (pin "2") (pinfunction "2_2") (pintype "passive"))
      (node (ref "R39") (pin "1") (pinfunction "1_1") (pintype "passive"))
      (node (ref "U13") (pin "13") (pinfunction "IN_D-_13") (pintype "input"))
    )
    (net (code "113") (name "Net-(U13D-OUT_D)") (class "Default")
      (node (ref "C47") (pin "1") (pinfunction "1_1") (pintype "passive"))
      (node (ref "R39") (pin "2") (pinfunction "2_2") (pintype "passive"))
      (node (ref "U13") (pin "14") (pinfunction "OUT_D_14") (pintype "output"))
    )
    (net (code "114") (name "unconnected-(J1-Pad7)") (class "Default")
      (node (ref "J1") (pin "7") (pinfunction "7_7") (pintype "passive+no_connect"))
    )
    (net (code "115") (name "unconnected-(MD1-+3V3-Pad17)") (class "Default")
      (node (ref "MD1") (pin "17") (pinfunction "+3V3_17") (pintype "power_in"))
    )
    (net (code "116") (name "unconnected-(MD1-A0-Pad19)") (class "Default")
      (node (ref "MD1") (pin "19") (pinfunction "A0_19") (pintype "bidirectional"))
    )
    (net (code "117") (name "unconnected-(MD1-A1-Pad20)") (class "Default")
      (node (ref "MD1") (pin "20") (pinfunction "A1_20") (pintype "bidirectional"))
    )
    (net (code "118") (name "unconnected-(MD1-A2-Pad21)") (class "Default")
      (node (ref "MD1") (pin "21") (pinfunction "A2_21") (pintype "bidirectional"))
    )
    (net (code "119") (name "unconnected-(MD1-A3-Pad22)") (class "Default")
      (node (ref "MD1") (pin "22") (pinfunction "A3_22") (pintype "bidirectional"))
    )
    (net (code "120") (name "unconnected-(MD1-A4-Pad23)") (class "Default")
      (node (ref "MD1") (pin "23") (pinfunction "A4_23") (pintype "bidirectional"))
    )
    (net (code "121") (name "unconnected-(MD1-A5-Pad24)") (class "Default")
      (node (ref "MD1") (pin "24") (pinfunction "A5_24") (pintype "bidirectional"))
    )
    (net (code "122") (name "unconnected-(MD1-A6-Pad25)") (class "Default")
      (node (ref "MD1") (pin "25") (pinfunction "A6_25") (pintype "bidirectional"))
    )
    (net (code "123") (name "unconnected-(MD1-A7-Pad26)") (class "Default")
      (node (ref "MD1") (pin "26") (pinfunction "A7_26") (pintype "bidirectional"))
    )
    (net (code "124") (name "unconnected-(MD1-AREF-Pad18)") (class "Default")
      (node (ref "MD1") (pin "18") (pinfunction "AREF_18") (pintype "passive"))
    )
    (net (code "125") (name "unconnected-(MD1-D0{slash}RX-Pad2)") (class "Default")
      (node (ref "MD1") (pin "2") (pinfunction "D0/RX_2") (pintype "bidirectional"))
    )
    (net (code "126") (name "unconnected-(MD1-D1{slash}TX-Pad1)") (class "Default")
      (node (ref "MD1") (pin "1") (pinfunction "D1/TX_1") (pintype "bidirectional"))
    )
    (net (code "127") (name "unconnected-(MD1-D10-Pad13)") (class "Default")
      (node (ref "MD1") (pin "13") (pinfunction "D10_13") (pintype "bidirectional"))
    )
    (net (code "128") (name "unconnected-(MD1-D11{slash}MOSI-Pad14)") (class "Default")
      (node (ref "MD1") (pin "14") (pinfunction "D11/MOSI_14") (pintype "bidirectional"))
    )
    (net (code "129") (name "unconnected-(MD1-~{RESET}-Pad28)") (class "Default")
      (node (ref "MD1") (pin "28") (pinfunction "~{RESET}_28") (pintype "passive"))
    )
    (net (code "130") (name "unconnected-(S1-Pad1)") (class "Default")
      (node (ref "S1") (pin "1") (pinfunction "1_1") (pintype "passive"))
    )
    (net (code "131") (name "unconnected-(S2-Pad1)") (class "Default")
      (node (ref "S2") (pin "1") (pinfunction "1_1") (pintype "passive"))
    )
    (net (code "132") (name "unconnected-(S3-Pad1)") (class "Default")
      (node (ref "S3") (pin "1") (pinfunction "1_1") (pintype "passive"))
    )
    (net (code "133") (name "unconnected-(S4-Pad1)") (class "Default")
      (node (ref "S4") (pin "1") (pinfunction "1_1") (pintype "passive"))
    )
    (net (code "134") (name "unconnected-(U14-SDO-Pad16)") (class "Default")
      (node (ref "U14") (pin "16") (pinfunction "SDO_16") (pintype "output+no_connect"))
    )
    (net (code "135") (name "unconnected-(U14-~{WP}-Pad14)") (class "Default")
      (node (ref "U14") (pin "14") (pinfunction "~{WP}_14") (pintype "input+no_connect"))
    )
    (net (code "136") (name "unconnected-(U15-SDO-Pad16)") (class "Default")
      (node (ref "U15") (pin "16") (pinfunction "SDO_16") (pintype "output+no_connect"))
    )
    (net (code "137") (name "unconnected-(U15-~{WP}-Pad14)") (class "Default")
      (node (ref "U15") (pin "14") (pinfunction "~{WP}_14") (pintype "input+no_connect"))
    )
    (net (code "138") (name "unconnected-(U16-SDO-Pad16)") (class "Default")
      (node (ref "U16") (pin "16") (pinfunction "SDO_16") (pintype "output+no_connect"))
    )
    (net (code "139") (name "unconnected-(U16-~{WP}-Pad14)") (class "Default")
      (node (ref "U16") (pin "14") (pinfunction "~{WP}_14") (pintype "input+no_connect"))
    )
    (net (code "140") (name "unconnected-(U17-SDO-Pad16)") (class "Default")
      (node (ref "U17") (pin "16") (pinfunction "SDO_16") (pintype "output+no_connect"))
    )
    (net (code "141") (name "unconnected-(U17-~{WP}-Pad14)") (class "Default")
      (node (ref "U17") (pin "14") (pinfunction "~{WP}_14") (pintype "input+no_connect"))
    )
    (net (code "142") (name "unconnected-(U18-SDO-Pad16)") (class "Default")
      (node (ref "U18") (pin "16") (pinfunction "SDO_16") (pintype "output+no_connect"))
    )
    (net (code "143") (name "unconnected-(U18-~{WP}-Pad14)") (class "Default")
      (node (ref "U18") (pin "14") (pinfunction "~{WP}_14") (pintype "input+no_connect"))
    )
    (net (code "144") (name "unconnected-(U19-SDO-Pad16)") (class "Default")
      (node (ref "U19") (pin "16") (pinfunction "SDO_16") (pintype "output+no_connect"))
    )
    (net (code "145") (name "unconnected-(U19-~{WP}-Pad14)") (class "Default")
      (node (ref "U19") (pin "14") (pinfunction "~{WP}_14") (pintype "input+no_connect"))
    )
    (net (code "146") (name "unconnected-(U20-SDO-Pad16)") (class "Default")
      (node (ref "U20") (pin "16") (pinfunction "SDO_16") (pintype "output+no_connect"))
    )
    (net (code "147") (name "unconnected-(U20-~{WP}-Pad14)") (class "Default")
      (node (ref "U20") (pin "14") (pinfunction "~{WP}_14") (pintype "input+no_connect"))
    )
    (net (code "148") (name "unconnected-(U21-SDO-Pad16)") (class "Default")
      (node (ref "U21") (pin "16") (pinfunction "SDO_16") (pintype "output+no_connect"))
    )
    (net (code "149") (name "unconnected-(U21-~{WP}-Pad14)") (class "Default")
      (node (ref "U21") (pin "14") (pinfunction "~{WP}_14") (pintype "input+no_connect"))
    )
  )
)
